# tracker.net
KiCad netlist of a schematic drawn in EAGLE
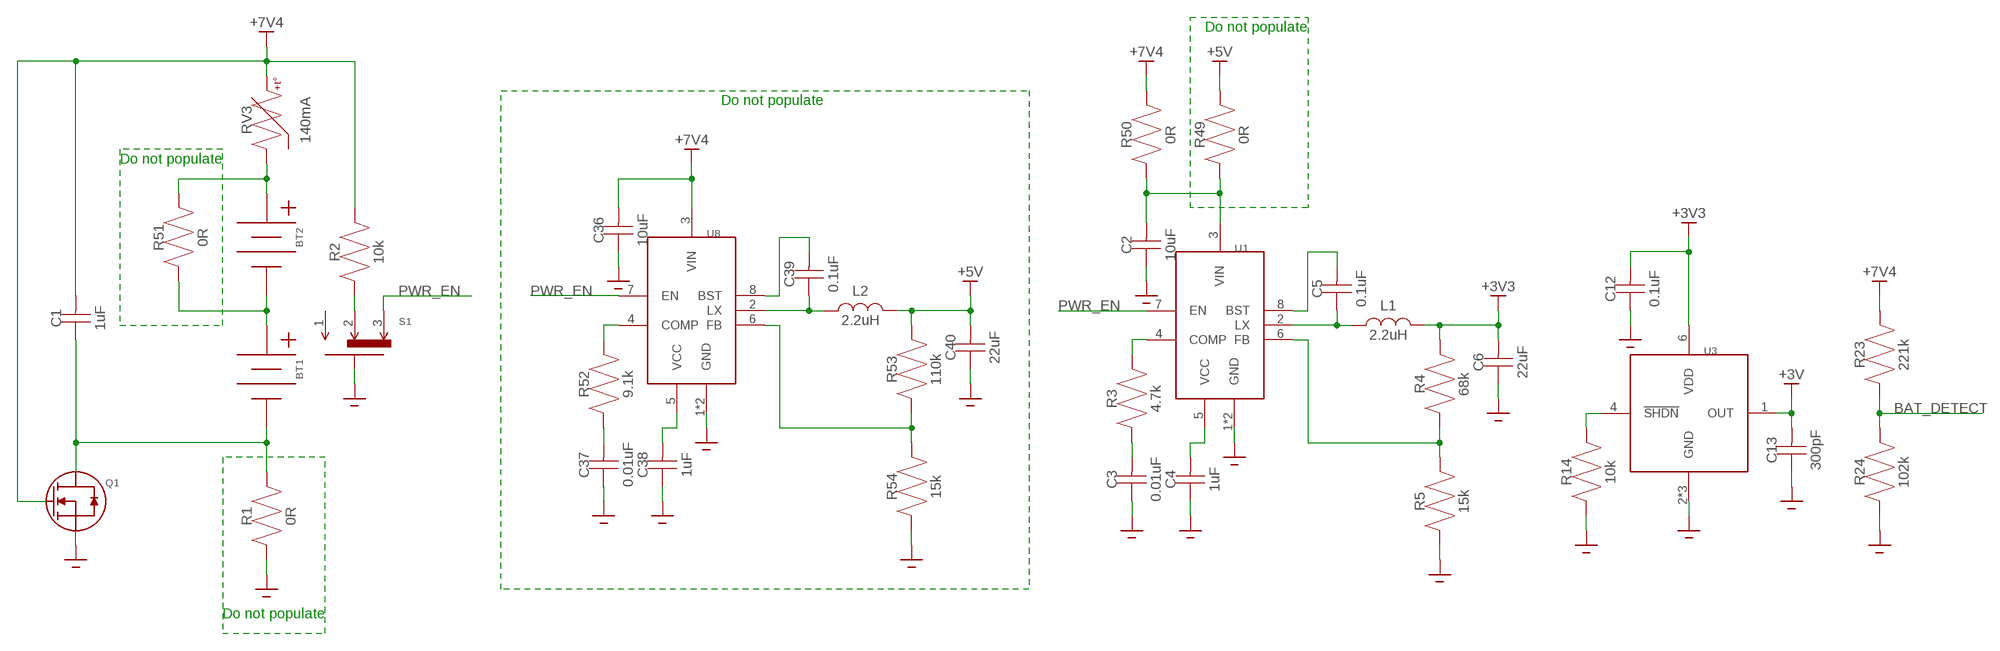
[diagram p0: schematic, sheet 1]
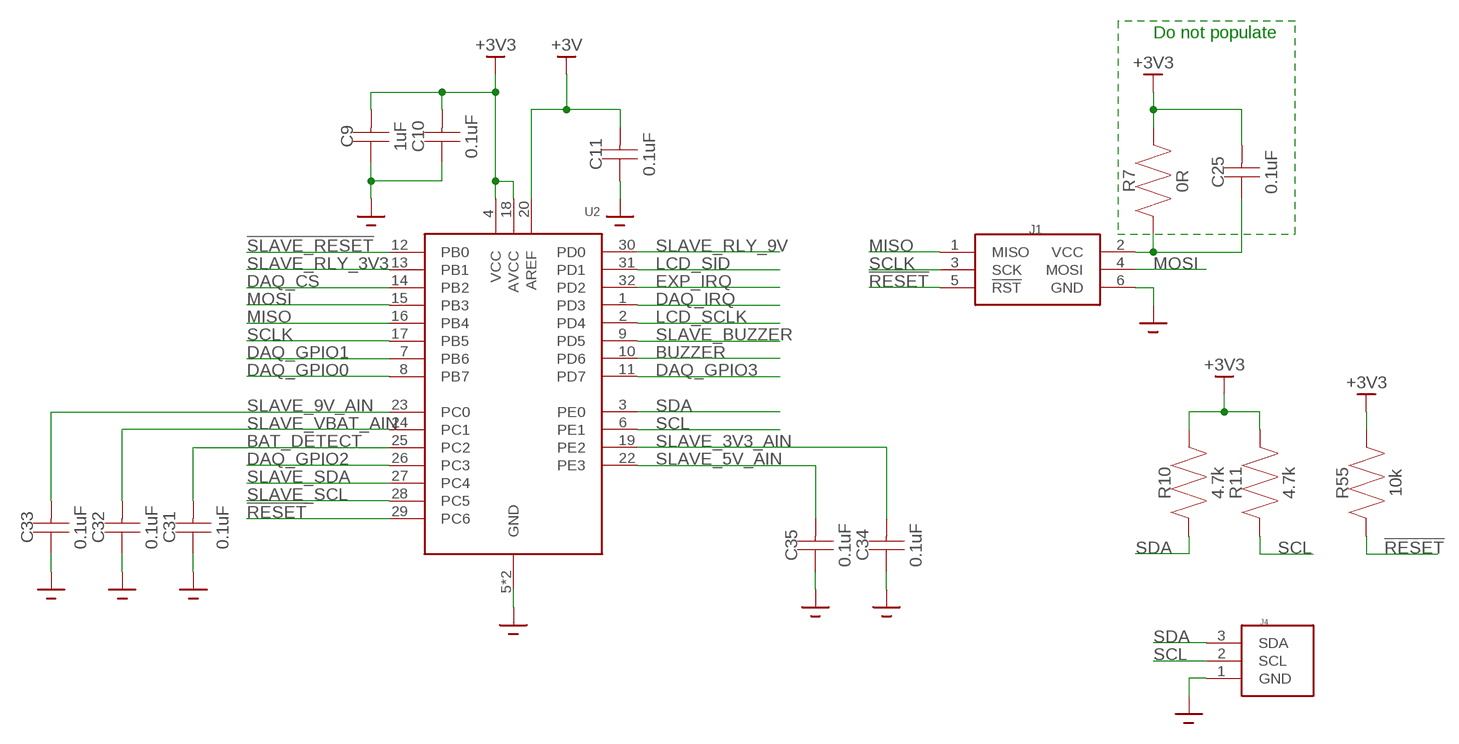
[diagram p1: schematic, sheet 2]
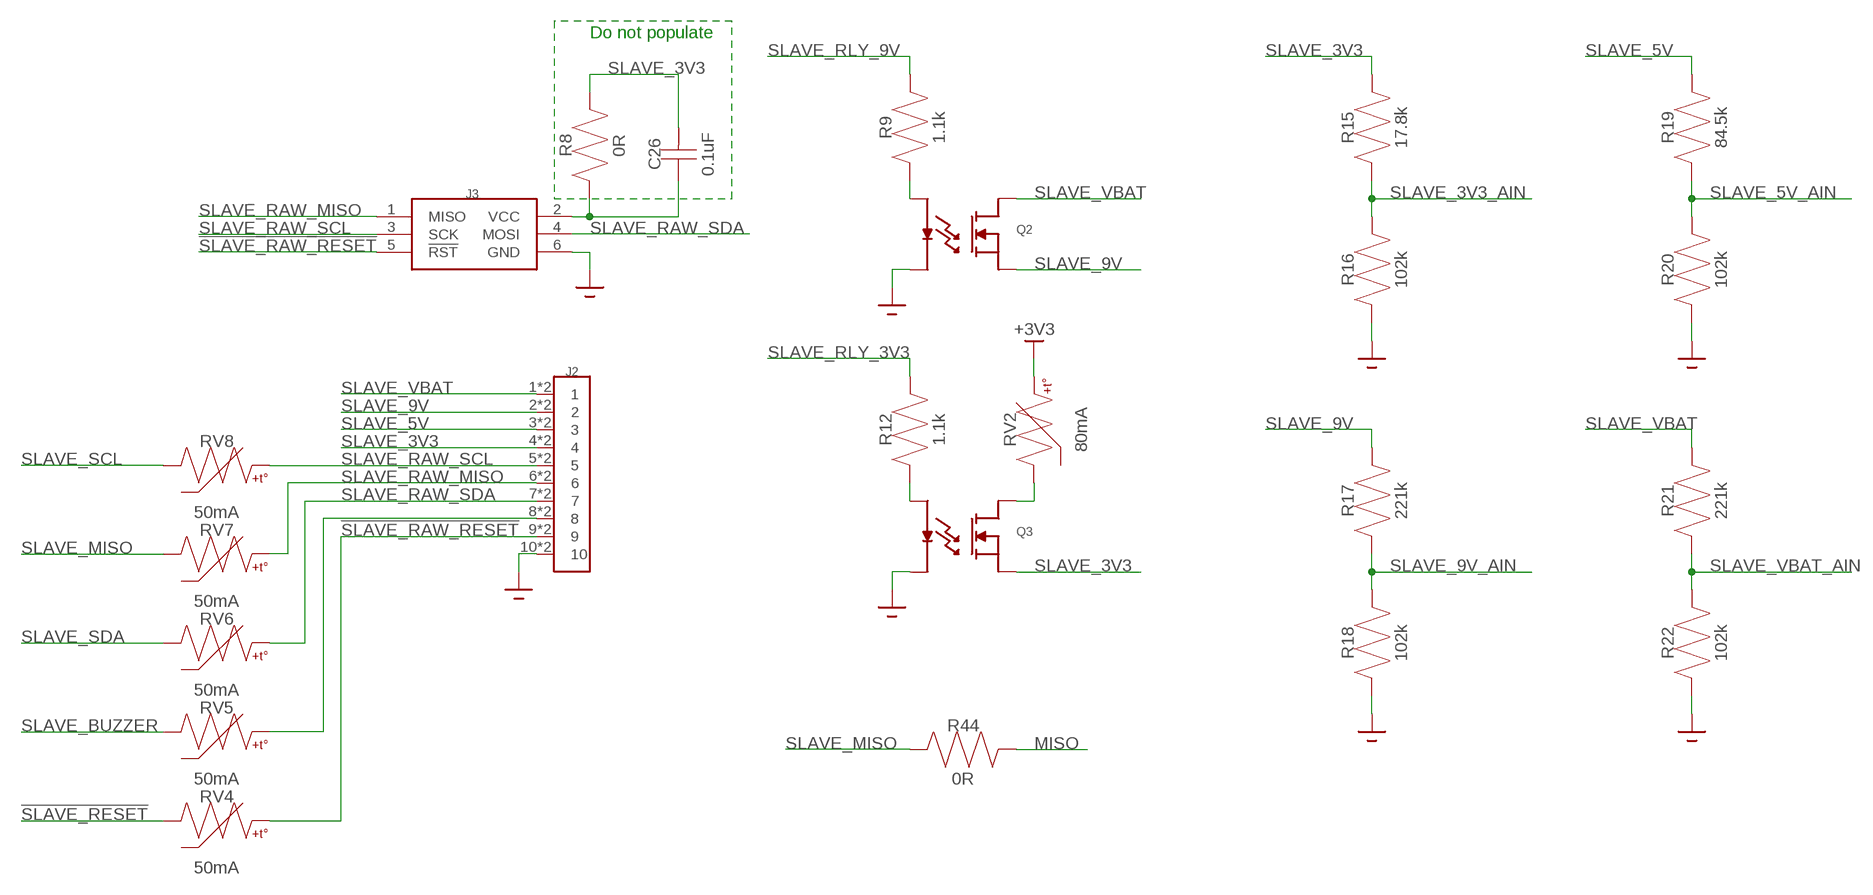
[diagram p2: schematic, sheet 3]
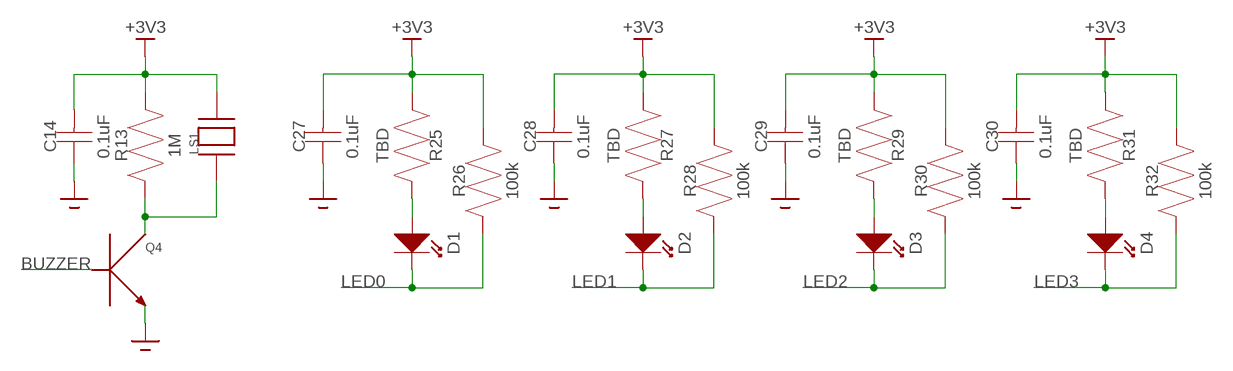
[diagram p3: schematic, sheet 4]
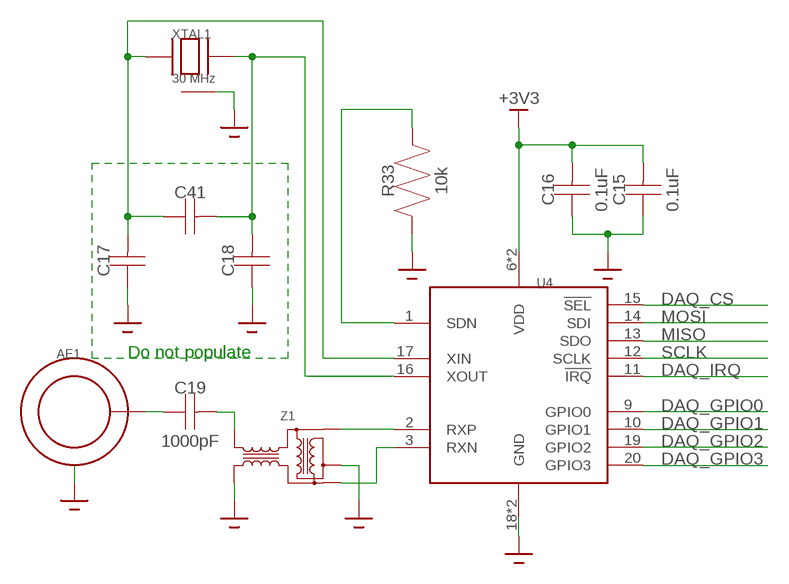
[diagram p4: schematic, sheet 5]
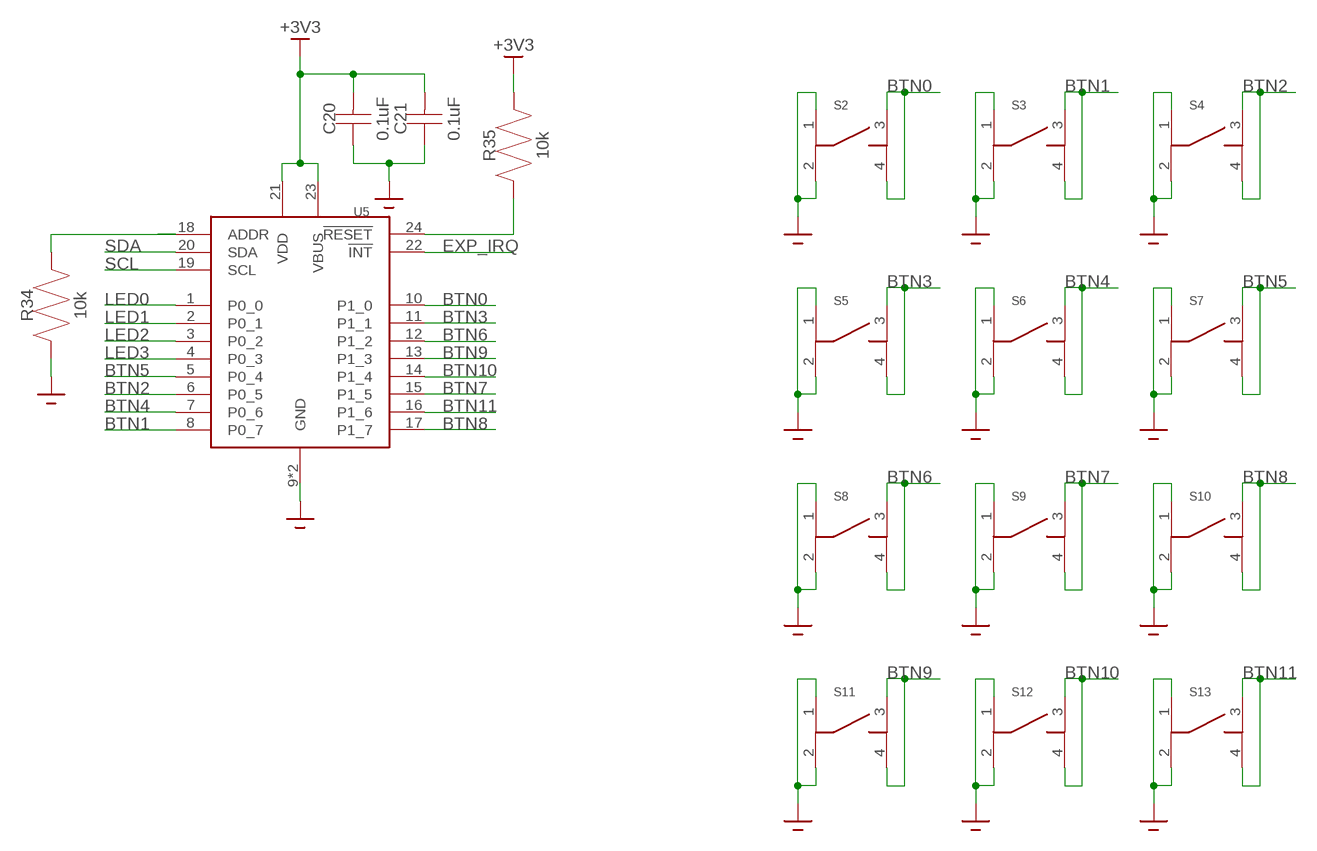
[diagram p5: schematic, sheet 6]
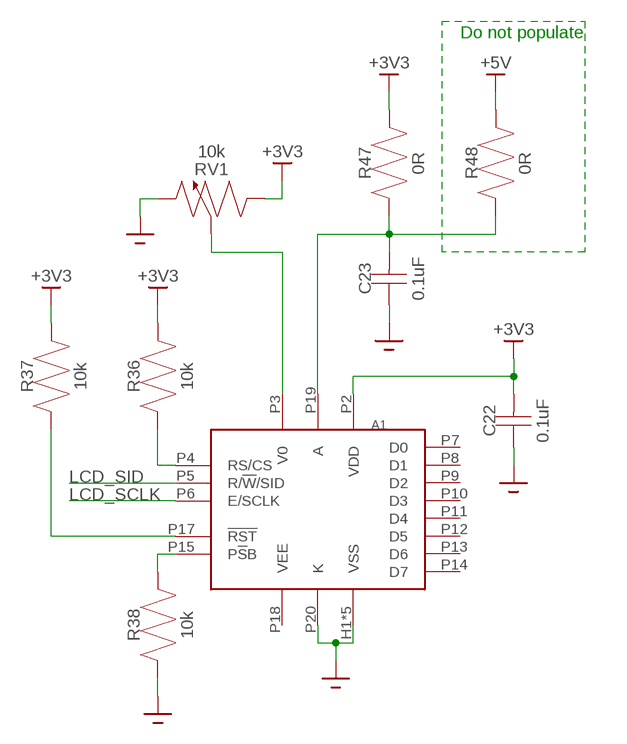
[diagram p6: schematic, sheet 7]
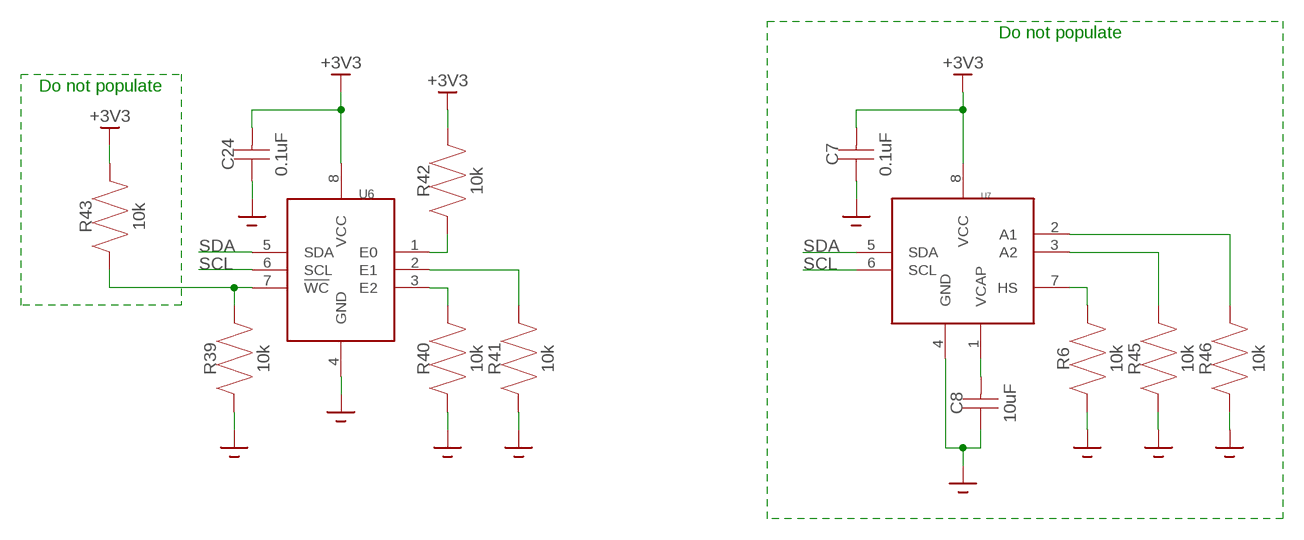
[diagram p7: schematic, sheet 8]

(export (version "E")
  (design (tool "Eeschema 10.0.6"))
  (components
    (comp (ref "A1")
      (value "LCD12864")
      (footprint "eagle-import:LCD12864")
      (libsource (lib "eagle-import") (part "LCD12864"))
    )
    (comp (ref "C22")
      (value "0.1uF")
      (footprint "eagle-import:0603")
      (libsource (lib "eagle-import") (part "CAPACITOR0603"))
    )
    (comp (ref "C23")
      (value "0.1uF")
      (footprint "eagle-import:0603")
      (libsource (lib "eagle-import") (part "CAPACITOR0603"))
    )
    (comp (ref "R36")
      (value "10k")
      (footprint "eagle-import:0603")
      (libsource (lib "eagle-import") (part "RESISTOR0603"))
    )
    (comp (ref "R37")
      (value "10k")
      (footprint "eagle-import:0603")
      (libsource (lib "eagle-import") (part "RESISTOR0603"))
    )
    (comp (ref "R38")
      (value "10k")
      (footprint "eagle-import:0603")
      (libsource (lib "eagle-import") (part "RESISTOR0603"))
    )
    (comp (ref "R47")
      (value "0R")
      (footprint "eagle-import:0603")
      (libsource (lib "eagle-import") (part "RESISTOR0603"))
    )
    (comp (ref "R48")
      (value "0R")
      (footprint "eagle-import:0603")
      (libsource (lib "eagle-import") (part "RESISTOR0603"))
    )
    (comp (ref "RV1")
      (value "10k")
      (footprint "eagle-import:TC33X-2")
      (libsource (lib "eagle-import") (part "TC33X-2"))
    )
    (comp (ref "C14")
      (value "0.1uF")
      (footprint "eagle-import:0603")
      (libsource (lib "eagle-import") (part "CAPACITOR0603"))
    )
    (comp (ref "C27")
      (value "0.1uF")
      (footprint "eagle-import:0603")
      (libsource (lib "eagle-import") (part "CAPACITOR0603"))
    )
    (comp (ref "C28")
      (value "0.1uF")
      (footprint "eagle-import:0603")
      (libsource (lib "eagle-import") (part "CAPACITOR0603"))
    )
    (comp (ref "C29")
      (value "0.1uF")
      (footprint "eagle-import:0603")
      (libsource (lib "eagle-import") (part "CAPACITOR0603"))
    )
    (comp (ref "C30")
      (value "0.1uF")
      (footprint "eagle-import:0603")
      (libsource (lib "eagle-import") (part "CAPACITOR0603"))
    )
    (comp (ref "D1")
      (value "LED")
      (footprint "eagle-import:0805")
      (libsource (lib "eagle-import") (part "LED"))
    )
    (comp (ref "D2")
      (value "LED")
      (footprint "eagle-import:0805")
      (libsource (lib "eagle-import") (part "LED"))
    )
    (comp (ref "D3")
      (value "LED")
      (footprint "eagle-import:0805")
      (libsource (lib "eagle-import") (part "LED"))
    )
    (comp (ref "D4")
      (value "LED")
      (footprint "eagle-import:0805")
      (libsource (lib "eagle-import") (part "LED"))
    )
    (comp (ref "LS1")
      (value "AT-1224-TWT-5V-2-R")
      (footprint "eagle-import:AT-1224-TWT-5V-2-R")
      (libsource (lib "eagle-import") (part "AT-1224-TWT-5V-2-R"))
    )
    (comp (ref "Q4")
      (value "MMBT3904")
      (footprint "eagle-import:MMBT3904")
      (libsource (lib "eagle-import") (part "MMBT3904"))
    )
    (comp (ref "R13")
      (value "1M")
      (footprint "eagle-import:0603")
      (libsource (lib "eagle-import") (part "RESISTOR0603"))
    )
    (comp (ref "R25")
      (value "TBD")
      (footprint "eagle-import:0603")
      (libsource (lib "eagle-import") (part "RESISTOR0603"))
    )
    (comp (ref "R26")
      (value "100k")
      (footprint "eagle-import:0603")
      (libsource (lib "eagle-import") (part "RESISTOR0603"))
    )
    (comp (ref "R27")
      (value "TBD")
      (footprint "eagle-import:0603")
      (libsource (lib "eagle-import") (part "RESISTOR0603"))
    )
    (comp (ref "R28")
      (value "100k")
      (footprint "eagle-import:0603")
      (libsource (lib "eagle-import") (part "RESISTOR0603"))
    )
    (comp (ref "R29")
      (value "TBD")
      (footprint "eagle-import:0603")
      (libsource (lib "eagle-import") (part "RESISTOR0603"))
    )
    (comp (ref "R30")
      (value "100k")
      (footprint "eagle-import:0603")
      (libsource (lib "eagle-import") (part "RESISTOR0603"))
    )
    (comp (ref "R31")
      (value "TBD")
      (footprint "eagle-import:0603")
      (libsource (lib "eagle-import") (part "RESISTOR0603"))
    )
    (comp (ref "R32")
      (value "100k")
      (footprint "eagle-import:0603")
      (libsource (lib "eagle-import") (part "RESISTOR0603"))
    )
    (comp (ref "AE1")
      (value "CON-SMA-EDGE-S")
      (footprint "eagle-import:CON-SMA-EDGE-S")
      (libsource (lib "eagle-import") (part "CON-SMA-EDGE-S"))
    )
    (comp (ref "C15")
      (value "0.1uF")
      (footprint "eagle-import:0603")
      (libsource (lib "eagle-import") (part "CAPACITOR0603"))
    )
    (comp (ref "C16")
      (value "0.1uF")
      (footprint "eagle-import:0603")
      (libsource (lib "eagle-import") (part "CAPACITOR0603"))
    )
    (comp (ref "C17")
      (value "CAPACITOR0603")
      (footprint "eagle-import:0603")
      (libsource (lib "eagle-import") (part "CAPACITOR0603"))
    )
    (comp (ref "C18")
      (value "CAPACITOR0603")
      (footprint "eagle-import:0603")
      (libsource (lib "eagle-import") (part "CAPACITOR0603"))
    )
    (comp (ref "C19")
      (value "1000pF")
      (footprint "eagle-import:0402")
      (libsource (lib "eagle-import") (part "CAPACITOR0402"))
    )
    (comp (ref "C41")
      (value "CAPACITOR0603")
      (footprint "eagle-import:0603")
      (libsource (lib "eagle-import") (part "CAPACITOR0603"))
    )
    (comp (ref "R33")
      (value "10k")
      (footprint "eagle-import:0603")
      (libsource (lib "eagle-import") (part "RESISTOR0603"))
    )
    (comp (ref "U4")
      (value "SI4362")
      (footprint "eagle-import:SI4362")
      (libsource (lib "eagle-import") (part "SI4362"))
    )
    (comp (ref "XTAL1")
      (value "30 MHz")
      (footprint "eagle-import:RH100")
      (libsource (lib "eagle-import") (part "RH100"))
    )
    (comp (ref "Z1")
      (value "TC1-1T-152X+")
      (footprint "eagle-import:TC1-1T-152X+")
      (libsource (lib "eagle-import") (part "TC1-1T-152X+"))
    )
    (comp (ref "C26")
      (value "0.1uF")
      (footprint "eagle-import:0603")
      (libsource (lib "eagle-import") (part "CAPACITOR0603"))
    )
    (comp (ref "J2")
      (value "5-5530843-0FEMALE")
      (footprint "eagle-import:5-5530843-0")
      (libsource (lib "eagle-import") (part "5-5530843-0FEMALE"))
    )
    (comp (ref "J3")
      (value "75869-131LF")
      (footprint "eagle-import:75869-131LF")
      (libsource (lib "eagle-import") (part "75869-131LF"))
    )
    (comp (ref "Q2")
      (value "CPC1002N")
      (footprint "eagle-import:CPC1002N")
      (libsource (lib "eagle-import") (part "CPC1002N"))
    )
    (comp (ref "Q3")
      (value "CPC1002N")
      (footprint "eagle-import:CPC1002N")
      (libsource (lib "eagle-import") (part "CPC1002N"))
    )
    (comp (ref "R8")
      (value "0R")
      (footprint "eagle-import:0603")
      (libsource (lib "eagle-import") (part "RESISTOR0603"))
    )
    (comp (ref "R9")
      (value "1.1k")
      (footprint "eagle-import:0603")
      (libsource (lib "eagle-import") (part "RESISTOR0603"))
    )
    (comp (ref "R12")
      (value "1.1k")
      (footprint "eagle-import:0603")
      (libsource (lib "eagle-import") (part "RESISTOR0603"))
    )
    (comp (ref "R15")
      (value "17.8k")
      (footprint "eagle-import:0603")
      (libsource (lib "eagle-import") (part "RESISTOR0603"))
    )
    (comp (ref "R16")
      (value "102k")
      (footprint "eagle-import:0603")
      (libsource (lib "eagle-import") (part "RESISTOR0603"))
    )
    (comp (ref "R17")
      (value "221k")
      (footprint "eagle-import:0603")
      (libsource (lib "eagle-import") (part "RESISTOR0603"))
    )
    (comp (ref "R18")
      (value "102k")
      (footprint "eagle-import:0603")
      (libsource (lib "eagle-import") (part "RESISTOR0603"))
    )
    (comp (ref "R19")
      (value "84.5k")
      (footprint "eagle-import:0603")
      (libsource (lib "eagle-import") (part "RESISTOR0603"))
    )
    (comp (ref "R20")
      (value "102k")
      (footprint "eagle-import:0603")
      (libsource (lib "eagle-import") (part "RESISTOR0603"))
    )
    (comp (ref "R21")
      (value "221k")
      (footprint "eagle-import:0603")
      (libsource (lib "eagle-import") (part "RESISTOR0603"))
    )
    (comp (ref "R22")
      (value "102k")
      (footprint "eagle-import:0603")
      (libsource (lib "eagle-import") (part "RESISTOR0603"))
    )
    (comp (ref "R44")
      (value "0R")
      (footprint "eagle-import:0603")
      (libsource (lib "eagle-import") (part "RESISTOR0603"))
    )
    (comp (ref "RV2")
      (value "80mA")
      (footprint "eagle-import:0603")
      (libsource (lib "eagle-import") (part "PTC0603"))
    )
    (comp (ref "RV4")
      (value "50mA")
      (footprint "eagle-import:0603")
      (libsource (lib "eagle-import") (part "PTC0603"))
    )
    (comp (ref "RV5")
      (value "50mA")
      (footprint "eagle-import:0603")
      (libsource (lib "eagle-import") (part "PTC0603"))
    )
    (comp (ref "RV6")
      (value "50mA")
      (footprint "eagle-import:0603")
      (libsource (lib "eagle-import") (part "PTC0603"))
    )
    (comp (ref "RV7")
      (value "50mA")
      (footprint "eagle-import:0603")
      (libsource (lib "eagle-import") (part "PTC0603"))
    )
    (comp (ref "RV8")
      (value "50mA")
      (footprint "eagle-import:0603")
      (libsource (lib "eagle-import") (part "PTC0603"))
    )
    (comp (ref "C20")
      (value "0.1uF")
      (footprint "eagle-import:0603")
      (libsource (lib "eagle-import") (part "CAPACITOR0603"))
    )
    (comp (ref "C21")
      (value "0.1uF")
      (footprint "eagle-import:0603")
      (libsource (lib "eagle-import") (part "CAPACITOR0603"))
    )
    (comp (ref "R34")
      (value "10k")
      (footprint "eagle-import:0603")
      (libsource (lib "eagle-import") (part "RESISTOR0603"))
    )
    (comp (ref "R35")
      (value "10k")
      (footprint "eagle-import:0603")
      (libsource (lib "eagle-import") (part "RESISTOR0603"))
    )
    (comp (ref "S2")
      (value "3-1825910")
      (footprint "eagle-import:3-1825910")
      (libsource (lib "eagle-import") (part "3-1825910"))
    )
    (comp (ref "S3")
      (value "3-1825910")
      (footprint "eagle-import:3-1825910")
      (libsource (lib "eagle-import") (part "3-1825910"))
    )
    (comp (ref "S4")
      (value "3-1825910")
      (footprint "eagle-import:3-1825910")
      (libsource (lib "eagle-import") (part "3-1825910"))
    )
    (comp (ref "S5")
      (value "3-1825910")
      (footprint "eagle-import:3-1825910")
      (libsource (lib "eagle-import") (part "3-1825910"))
    )
    (comp (ref "S6")
      (value "3-1825910")
      (footprint "eagle-import:3-1825910")
      (libsource (lib "eagle-import") (part "3-1825910"))
    )
    (comp (ref "S7")
      (value "3-1825910")
      (footprint "eagle-import:3-1825910")
      (libsource (lib "eagle-import") (part "3-1825910"))
    )
    (comp (ref "S8")
      (value "3-1825910")
      (footprint "eagle-import:3-1825910")
      (libsource (lib "eagle-import") (part "3-1825910"))
    )
    (comp (ref "S9")
      (value "3-1825910")
      (footprint "eagle-import:3-1825910")
      (libsource (lib "eagle-import") (part "3-1825910"))
    )
    (comp (ref "S10")
      (value "3-1825910")
      (footprint "eagle-import:3-1825910")
      (libsource (lib "eagle-import") (part "3-1825910"))
    )
    (comp (ref "S11")
      (value "3-1825910")
      (footprint "eagle-import:3-1825910")
      (libsource (lib "eagle-import") (part "3-1825910"))
    )
    (comp (ref "S12")
      (value "3-1825910")
      (footprint "eagle-import:3-1825910")
      (libsource (lib "eagle-import") (part "3-1825910"))
    )
    (comp (ref "S13")
      (value "3-1825910")
      (footprint "eagle-import:3-1825910")
      (libsource (lib "eagle-import") (part "3-1825910"))
    )
    (comp (ref "U5")
      (value "PCAL6416")
      (footprint "eagle-import:PCAL6416")
      (libsource (lib "eagle-import") (part "PCAL6416"))
    )
    (comp (ref "BT1")
      (value "18650")
      (footprint "eagle-import:18650")
      (libsource (lib "eagle-import") (part "18650"))
    )
    (comp (ref "BT2")
      (value "18650")
      (footprint "eagle-import:18650")
      (libsource (lib "eagle-import") (part "18650"))
    )
    (comp (ref "C1")
      (value "1uF")
      (footprint "eagle-import:0603")
      (libsource (lib "eagle-import") (part "CAPACITOR0603"))
    )
    (comp (ref "C2")
      (value "10uF")
      (footprint "eagle-import:0805")
      (libsource (lib "eagle-import") (part "CAPACITOR0805"))
    )
    (comp (ref "C3")
      (value "0.01uF")
      (footprint "eagle-import:0603")
      (libsource (lib "eagle-import") (part "CAPACITOR0603"))
    )
    (comp (ref "C4")
      (value "1uF")
      (footprint "eagle-import:0603")
      (libsource (lib "eagle-import") (part "CAPACITOR0603"))
    )
    (comp (ref "C5")
      (value "0.1uF")
      (footprint "eagle-import:0603")
      (libsource (lib "eagle-import") (part "CAPACITOR0603"))
    )
    (comp (ref "C6")
      (value "22uF")
      (footprint "eagle-import:0805")
      (libsource (lib "eagle-import") (part "CAPACITOR0805"))
    )
    (comp (ref "C12")
      (value "0.1uF")
      (footprint "eagle-import:0603")
      (libsource (lib "eagle-import") (part "CAPACITOR0603"))
    )
    (comp (ref "C13")
      (value "300pF")
      (footprint "eagle-import:0603")
      (libsource (lib "eagle-import") (part "CAPACITOR0603"))
    )
    (comp (ref "C36")
      (value "10uF")
      (footprint "eagle-import:0805")
      (libsource (lib "eagle-import") (part "CAPACITOR0805"))
    )
    (comp (ref "C37")
      (value "0.01uF")
      (footprint "eagle-import:0603")
      (libsource (lib "eagle-import") (part "CAPACITOR0603"))
    )
    (comp (ref "C38")
      (value "1uF")
      (footprint "eagle-import:0603")
      (libsource (lib "eagle-import") (part "CAPACITOR0603"))
    )
    (comp (ref "C39")
      (value "0.1uF")
      (footprint "eagle-import:0603")
      (libsource (lib "eagle-import") (part "CAPACITOR0603"))
    )
    (comp (ref "C40")
      (value "22uF")
      (footprint "eagle-import:0805")
      (libsource (lib "eagle-import") (part "CAPACITOR0805"))
    )
    (comp (ref "L1")
      (value "2.2uH")
      (footprint "eagle-import:0805")
      (libsource (lib "eagle-import") (part "INDUCTOR0805"))
    )
    (comp (ref "L2")
      (value "2.2uH")
      (footprint "eagle-import:0805")
      (libsource (lib "eagle-import") (part "INDUCTOR0805"))
    )
    (comp (ref "Q1")
      (value "DMG2302UK")
      (footprint "eagle-import:DMG2302UK")
      (libsource (lib "eagle-import") (part "DMG2302UK"))
    )
    (comp (ref "R1")
      (value "0R")
      (footprint "eagle-import:0603")
      (libsource (lib "eagle-import") (part "RESISTOR0603"))
    )
    (comp (ref "R2")
      (value "10k")
      (footprint "eagle-import:0603")
      (libsource (lib "eagle-import") (part "RESISTOR0603"))
    )
    (comp (ref "R3")
      (value "4.7k")
      (footprint "eagle-import:0603")
      (libsource (lib "eagle-import") (part "RESISTOR0603"))
    )
    (comp (ref "R4")
      (value "68k")
      (footprint "eagle-import:0603")
      (libsource (lib "eagle-import") (part "RESISTOR0603"))
    )
    (comp (ref "R5")
      (value "15k")
      (footprint "eagle-import:0603")
      (libsource (lib "eagle-import") (part "RESISTOR0603"))
    )
    (comp (ref "R14")
      (value "10k")
      (footprint "eagle-import:0603")
      (libsource (lib "eagle-import") (part "RESISTOR0603"))
    )
    (comp (ref "R23")
      (value "221k")
      (footprint "eagle-import:0603")
      (libsource (lib "eagle-import") (part "RESISTOR0603"))
    )
    (comp (ref "R24")
      (value "102k")
      (footprint "eagle-import:0603")
      (libsource (lib "eagle-import") (part "RESISTOR0603"))
    )
    (comp (ref "R49")
      (value "0R")
      (footprint "eagle-import:0603")
      (libsource (lib "eagle-import") (part "RESISTOR0603"))
    )
    (comp (ref "R50")
      (value "0R")
      (footprint "eagle-import:0603")
      (libsource (lib "eagle-import") (part "RESISTOR0603"))
    )
    (comp (ref "R51")
      (value "0R")
      (footprint "eagle-import:0603")
      (libsource (lib "eagle-import") (part "RESISTOR0603"))
    )
    (comp (ref "R52")
      (value "9.1k")
      (footprint "eagle-import:0603")
      (libsource (lib "eagle-import") (part "RESISTOR0603"))
    )
    (comp (ref "R53")
      (value "110k")
      (footprint "eagle-import:0603")
      (libsource (lib "eagle-import") (part "RESISTOR0603"))
    )
    (comp (ref "R54")
      (value "15k")
      (footprint "eagle-import:0603")
      (libsource (lib "eagle-import") (part "RESISTOR0603"))
    )
    (comp (ref "RV3")
      (value "140mA")
      (footprint "eagle-import:1812")
      (libsource (lib "eagle-import") (part "PTC1812"))
    )
    (comp (ref "S1")
      (value "OS102011MA1QN1")
      (footprint "eagle-import:OS102011MA1QN1")
      (libsource (lib "eagle-import") (part "OS102011MA1QN1"))
    )
    (comp (ref "U1")
      (value "AOZ6662DI")
      (footprint "eagle-import:AOZ6662DI")
      (libsource (lib "eagle-import") (part "AOZ6662DI"))
    )
    (comp (ref "U3")
      (value "MCP1501")
      (footprint "eagle-import:SOT95P280X145-6N")
      (libsource (lib "eagle-import") (part "MCP1501"))
    )
    (comp (ref "U8")
      (value "AOZ6662DI")
      (footprint "eagle-import:AOZ6662DI")
      (libsource (lib "eagle-import") (part "AOZ6662DI"))
    )
    (comp (ref "C9")
      (value "1uF")
      (footprint "eagle-import:0603")
      (libsource (lib "eagle-import") (part "CAPACITOR0603"))
    )
    (comp (ref "C10")
      (value "0.1uF")
      (footprint "eagle-import:0603")
      (libsource (lib "eagle-import") (part "CAPACITOR0603"))
    )
    (comp (ref "C11")
      (value "0.1uF")
      (footprint "eagle-import:0603")
      (libsource (lib "eagle-import") (part "CAPACITOR0603"))
    )
    (comp (ref "C25")
      (value "0.1uF")
      (footprint "eagle-import:0603")
      (libsource (lib "eagle-import") (part "CAPACITOR0603"))
    )
    (comp (ref "C31")
      (value "0.1uF")
      (footprint "eagle-import:0603")
      (libsource (lib "eagle-import") (part "CAPACITOR0603"))
    )
    (comp (ref "C32")
      (value "0.1uF")
      (footprint "eagle-import:0603")
      (libsource (lib "eagle-import") (part "CAPACITOR0603"))
    )
    (comp (ref "C33")
      (value "0.1uF")
      (footprint "eagle-import:0603")
      (libsource (lib "eagle-import") (part "CAPACITOR0603"))
    )
    (comp (ref "C34")
      (value "0.1uF")
      (footprint "eagle-import:0603")
      (libsource (lib "eagle-import") (part "CAPACITOR0603"))
    )
    (comp (ref "C35")
      (value "0.1uF")
      (footprint "eagle-import:0603")
      (libsource (lib "eagle-import") (part "CAPACITOR0603"))
    )
    (comp (ref "J1")
      (value "75869-131LF")
      (footprint "eagle-import:75869-131LF")
      (libsource (lib "eagle-import") (part "75869-131LF"))
    )
    (comp (ref "J4")
      (value "640456-3")
      (footprint "eagle-import:640456-3")
      (libsource (lib "eagle-import") (part "640456-3"))
    )
    (comp (ref "R7")
      (value "0R")
      (footprint "eagle-import:0603")
      (libsource (lib "eagle-import") (part "RESISTOR0603"))
    )
    (comp (ref "R10")
      (value "4.7k")
      (footprint "eagle-import:0603")
      (libsource (lib "eagle-import") (part "RESISTOR0603"))
    )
    (comp (ref "R11")
      (value "4.7k")
      (footprint "eagle-import:0603")
      (libsource (lib "eagle-import") (part "RESISTOR0603"))
    )
    (comp (ref "R55")
      (value "10k")
      (footprint "eagle-import:0603")
      (libsource (lib "eagle-import") (part "RESISTOR0603"))
    )
    (comp (ref "U2")
      (value "ATMEGA328PB32-TQFP")
      (footprint "eagle-import:ATMEGA328PB")
      (libsource (lib "eagle-import") (part "ATMEGA328PB32-TQFP"))
    )
    (comp (ref "C7")
      (value "0.1uF")
      (footprint "eagle-import:0603")
      (libsource (lib "eagle-import") (part "CAPACITOR0603"))
    )
    (comp (ref "C8")
      (value "10uF")
      (footprint "eagle-import:0805")
      (libsource (lib "eagle-import") (part "CAPACITOR0805"))
    )
    (comp (ref "C24")
      (value "0.1uF")
      (footprint "eagle-import:0603")
      (libsource (lib "eagle-import") (part "CAPACITOR0603"))
    )
    (comp (ref "R6")
      (value "10k")
      (footprint "eagle-import:0603")
      (libsource (lib "eagle-import") (part "RESISTOR0603"))
    )
    (comp (ref "R39")
      (value "10k")
      (footprint "eagle-import:0603")
      (libsource (lib "eagle-import") (part "RESISTOR0603"))
    )
    (comp (ref "R40")
      (value "10k")
      (footprint "eagle-import:0603")
      (libsource (lib "eagle-import") (part "RESISTOR0603"))
    )
    (comp (ref "R41")
      (value "10k")
      (footprint "eagle-import:0603")
      (libsource (lib "eagle-import") (part "RESISTOR0603"))
    )
    (comp (ref "R42")
      (value "10k")
      (footprint "eagle-import:0603")
      (libsource (lib "eagle-import") (part "RESISTOR0603"))
    )
    (comp (ref "R43")
      (value "10k")
      (footprint "eagle-import:0603")
      (libsource (lib "eagle-import") (part "RESISTOR0603"))
    )
    (comp (ref "R45")
      (value "10k")
      (footprint "eagle-import:0603")
      (libsource (lib "eagle-import") (part "RESISTOR0603"))
    )
    (comp (ref "R46")
      (value "10k")
      (footprint "eagle-import:0603")
      (libsource (lib "eagle-import") (part "RESISTOR0603"))
    )
    (comp (ref "U6")
      (value "M24")
      (footprint "eagle-import:M24")
      (libsource (lib "eagle-import") (part "M24"))
    )
    (comp (ref "U7")
      (value "47L16")
      (footprint "eagle-import:47L16")
      (libsource (lib "eagle-import") (part "47L16"))
    )
  )
  (nets
    (net (code "1") (name "+3V") (class "Default")
      (node (ref "C11") (pin "P$2") (pinfunction "P$2_P$2") (pintype "passive"))
      (node (ref "C13") (pin "P$2") (pinfunction "P$2_P$2") (pintype "passive"))
      (node (ref "U2") (pin "20") (pinfunction "AREF_20") (pintype "power_in"))
      (node (ref "U3") (pin "1") (pinfunction "OUT_1") (pintype "power_in"))
    )
    (net (code "2") (name "+3V3") (class "Default")
      (node (ref "A1") (pin "P2") (pinfunction "VDD_P2") (pintype "power_in"))
      (node (ref "C10") (pin "P$2") (pinfunction "P$2_P$2") (pintype "passive"))
      (node (ref "C12") (pin "P$2") (pinfunction "P$2_P$2") (pintype "passive"))
      (node (ref "C14") (pin "P$2") (pinfunction "P$2_P$2") (pintype "passive"))
      (node (ref "C15") (pin "P$2") (pinfunction "P$2_P$2") (pintype "passive"))
      (node (ref "C16") (pin "P$2") (pinfunction "P$2_P$2") (pintype "passive"))
      (node (ref "C20") (pin "P$2") (pinfunction "P$2_P$2") (pintype "passive"))
      (node (ref "C21") (pin "P$2") (pinfunction "P$2_P$2") (pintype "passive"))
      (node (ref "C22") (pin "P$2") (pinfunction "P$2_P$2") (pintype "passive"))
      (node (ref "C24") (pin "P$2") (pinfunction "P$2_P$2") (pintype "passive"))
      (node (ref "C25") (pin "P$2") (pinfunction "P$2_P$2") (pintype "passive"))
      (node (ref "C27") (pin "P$2") (pinfunction "P$2_P$2") (pintype "passive"))
      (node (ref "C28") (pin "P$2") (pinfunction "P$2_P$2") (pintype "passive"))
      (node (ref "C29") (pin "P$2") (pinfunction "P$2_P$2") (pintype "passive"))
      (node (ref "C30") (pin "P$2") (pinfunction "P$2_P$2") (pintype "passive"))
      (node (ref "C6") (pin "P$2") (pinfunction "P$2_P$2") (pintype "passive"))
      (node (ref "C7") (pin "P$2") (pinfunction "P$2_P$2") (pintype "passive"))
      (node (ref "C9") (pin "P$2") (pinfunction "P$2_P$2") (pintype "passive"))
      (node (ref "L1") (pin "P$2") (pinfunction "P$2_P$2") (pintype "passive"))
      (node (ref "LS1") (pin "2") (pinfunction "P$2_2") (pintype "passive"))
      (node (ref "R10") (pin "P$2") (pinfunction "P$2_P$2") (pintype "passive"))
      (node (ref "R11") (pin "P$2") (pinfunction "P$2_P$2") (pintype "passive"))
      (node (ref "R13") (pin "P$2") (pinfunction "P$2_P$2") (pintype "passive"))
      (node (ref "R25") (pin "P$1") (pinfunction "P$1_P$1") (pintype "passive"))
      (node (ref "R26") (pin "P$2") (pinfunction "P$2_P$2") (pintype "passive"))
      (node (ref "R27") (pin "P$1") (pinfunction "P$1_P$1") (pintype "passive"))
      (node (ref "R28") (pin "P$2") (pinfunction "P$2_P$2") (pintype "passive"))
      (node (ref "R29") (pin "P$1") (pinfunction "P$1_P$1") (pintype "passive"))
      (node (ref "R30") (pin "P$2") (pinfunction "P$2_P$2") (pintype "passive"))
      (node (ref "R31") (pin "P$1") (pinfunction "P$1_P$1") (pintype "passive"))
      (node (ref "R32") (pin "P$2") (pinfunction "P$2_P$2") (pintype "passive"))
      (node (ref "R35") (pin "P$2") (pinfunction "P$2_P$2") (pintype "passive"))
      (node (ref "R36") (pin "P$2") (pinfunction "P$2_P$2") (pintype "passive"))
      (node (ref "R37") (pin "P$2") (pinfunction "P$2_P$2") (pintype "passive"))
      (node (ref "R4") (pin "P$2") (pinfunction "P$2_P$2") (pintype "passive"))
      (node (ref "R42") (pin "P$2") (pinfunction "P$2_P$2") (pintype "passive"))
      (node (ref "R43") (pin "P$2") (pinfunction "P$2_P$2") (pintype "passive"))
      (node (ref "R47") (pin "P$2") (pinfunction "P$2_P$2") (pintype "passive"))
      (node (ref "R55") (pin "P$2") (pinfunction "P$2_P$2") (pintype "passive"))
      (node (ref "R7") (pin "P$2") (pinfunction "P$2_P$2") (pintype "passive"))
      (node (ref "RV1") (pin "1") (pinfunction "CCW_1") (pintype "passive"))
      (node (ref "RV2") (pin "P$2") (pinfunction "P$2_P$2") (pintype "passive"))
      (node (ref "U2") (pin "18") (pinfunction "AVCC_18") (pintype "power_in"))
      (node (ref "U2") (pin "4") (pinfunction "VCC_4") (pintype "power_in"))
      (node (ref "U3") (pin "6") (pinfunction "VDD_6") (pintype "power_in"))
      (node (ref "U4") (pin "6") (pinfunction "VDD_6") (pintype "power_in"))
      (node (ref "U4") (pin "8") (pinfunction "VDD_8") (pintype "power_in"))
      (node (ref "U5") (pin "21") (pinfunction "VDD_21") (pintype "power_in"))
      (node (ref "U5") (pin "23") (pinfunction "VBUS_23") (pintype "power_in"))
      (node (ref "U6") (pin "8") (pinfunction "VCC_8") (pintype "power_in"))
      (node (ref "U7") (pin "8") (pinfunction "VCC_8") (pintype "power_in"))
    )
    (net (code "3") (name "+5V") (class "Default")
      (node (ref "C40") (pin "P$2") (pinfunction "P$2_P$2") (pintype "passive"))
      (node (ref "L2") (pin "P$2") (pinfunction "P$2_P$2") (pintype "passive"))
      (node (ref "R48") (pin "P$2") (pinfunction "P$2_P$2") (pintype "passive"))
      (node (ref "R49") (pin "P$2") (pinfunction "P$2_P$2") (pintype "passive"))
      (node (ref "R53") (pin "P$2") (pinfunction "P$2_P$2") (pintype "passive"))
    )
    (net (code "4") (name "+7V4V") (class "Default")
      (node (ref "C1") (pin "P$2") (pinfunction "P$2_P$2") (pintype "passive"))
      (node (ref "C36") (pin "P$2") (pinfunction "P$2_P$2") (pintype "passive"))
      (node (ref "Q1") (pin "1") (pinfunction "G_1") (pintype "bidirectional"))
      (node (ref "R2") (pin "P$2") (pinfunction "P$2_P$2") (pintype "passive"))
      (node (ref "R23") (pin "P$2") (pinfunction "P$2_P$2") (pintype "passive"))
      (node (ref "R50") (pin "P$2") (pinfunction "P$2_P$2") (pintype "passive"))
      (node (ref "RV3") (pin "P$2") (pinfunction "P$2_P$2") (pintype "passive"))
      (node (ref "U8") (pin "3") (pinfunction "VIN_3") (pintype "power_in"))
    )
    (net (code "5") (name "BAT_DETECT") (class "Default")
      (node (ref "C31") (pin "P$2") (pinfunction "P$2_P$2") (pintype "passive"))
      (node (ref "R23") (pin "P$1") (pinfunction "P$1_P$1") (pintype "passive"))
      (node (ref "R24") (pin "P$2") (pinfunction "P$2_P$2") (pintype "passive"))
      (node (ref "U2") (pin "25") (pinfunction "PC2_25") (pintype "bidirectional"))
    )
    (net (code "6") (name "BTN0") (class "Default")
      (node (ref "S2") (pin "3") (pinfunction "4_3") (pintype "passive"))
      (node (ref "S2") (pin "4") (pinfunction "3_4") (pintype "passive"))
      (node (ref "U5") (pin "10") (pinfunction "P1_0_10") (pintype "bidirectional"))
    )
    (net (code "7") (name "BTN1") (class "Default")
      (node (ref "S3") (pin "3") (pinfunction "4_3") (pintype "passive"))
      (node (ref "S3") (pin "4") (pinfunction "3_4") (pintype "passive"))
      (node (ref "U5") (pin "8") (pinfunction "P0_7_8") (pintype "bidirectional"))
    )
    (net (code "8") (name "BTN2") (class "Default")
      (node (ref "S4") (pin "3") (pinfunction "4_3") (pintype "passive"))
      (node (ref "S4") (pin "4") (pinfunction "3_4") (pintype "passive"))
      (node (ref "U5") (pin "6") (pinfunction "P0_5_6") (pintype "bidirectional"))
    )
    (net (code "9") (name "BTN3") (class "Default")
      (node (ref "S5") (pin "3") (pinfunction "4_3") (pintype "passive"))
      (node (ref "S5") (pin "4") (pinfunction "3_4") (pintype "passive"))
      (node (ref "U5") (pin "11") (pinfunction "P1_1_11") (pintype "bidirectional"))
    )
    (net (code "10") (name "BTN4") (class "Default")
      (node (ref "S6") (pin "3") (pinfunction "4_3") (pintype "passive"))
      (node (ref "S6") (pin "4") (pinfunction "3_4") (pintype "passive"))
      (node (ref "U5") (pin "7") (pinfunction "P0_6_7") (pintype "bidirectional"))
    )
    (net (code "11") (name "BTN5") (class "Default")
      (node (ref "S7") (pin "3") (pinfunction "4_3") (pintype "passive"))
      (node (ref "S7") (pin "4") (pinfunction "3_4") (pintype "passive"))
      (node (ref "U5") (pin "5") (pinfunction "P0_4_5") (pintype "bidirectional"))
    )
    (net (code "12") (name "BTN6") (class "Default")
      (node (ref "S8") (pin "3") (pinfunction "4_3") (pintype "passive"))
      (node (ref "S8") (pin "4") (pinfunction "3_4") (pintype "passive"))
      (node (ref "U5") (pin "12") (pinfunction "P1_2_12") (pintype "bidirectional"))
    )
    (net (code "13") (name "BTN7") (class "Default")
      (node (ref "S9") (pin "3") (pinfunction "4_3") (pintype "passive"))
      (node (ref "S9") (pin "4") (pinfunction "3_4") (pintype "passive"))
      (node (ref "U5") (pin "15") (pinfunction "P1_5_15") (pintype "bidirectional"))
    )
    (net (code "14") (name "BTN8") (class "Default")
      (node (ref "S10") (pin "3") (pinfunction "4_3") (pintype "passive"))
      (node (ref "S10") (pin "4") (pinfunction "3_4") (pintype "passive"))
      (node (ref "U5") (pin "17") (pinfunction "P1_7_17") (pintype "bidirectional"))
    )
    (net (code "15") (name "BTN9") (class "Default")
      (node (ref "S11") (pin "3") (pinfunction "4_3") (pintype "passive"))
      (node (ref "S11") (pin "4") (pinfunction "3_4") (pintype "passive"))
      (node (ref "U5") (pin "13") (pinfunction "P1_3_13") (pintype "bidirectional"))
    )
    (net (code "16") (name "BTN10") (class "Default")
      (node (ref "S12") (pin "3") (pinfunction "4_3") (pintype "passive"))
      (node (ref "S12") (pin "4") (pinfunction "3_4") (pintype "passive"))
      (node (ref "U5") (pin "14") (pinfunction "P1_4_14") (pintype "bidirectional"))
    )
    (net (code "17") (name "BTN11") (class "Default")
      (node (ref "S13") (pin "3") (pinfunction "4_3") (pintype "passive"))
      (node (ref "S13") (pin "4") (pinfunction "3_4") (pintype "passive"))
      (node (ref "U5") (pin "16") (pinfunction "P1_6_16") (pintype "bidirectional"))
    )
    (net (code "18") (name "BUZZER") (class "Default")
      (node (ref "Q4") (pin "1") (pinfunction "B_1") (pintype "bidirectional"))
      (node (ref "U2") (pin "10") (pinfunction "PD6_10") (pintype "bidirectional"))
    )
    (net (code "19") (name "DAQ_CS") (class "Default")
      (node (ref "U2") (pin "14") (pinfunction "PB2_14") (pintype "bidirectional"))
      (node (ref "U4") (pin "15") (pinfunction "~{SEL}_15") (pintype "input"))
    )
    (net (code "20") (name "DAQ_GPIO0") (class "Default")
      (node (ref "U2") (pin "8") (pinfunction "PB7_8") (pintype "bidirectional"))
      (node (ref "U4") (pin "9") (pinfunction "GPIO0_9") (pintype "bidirectional"))
    )
    (net (code "21") (name "DAQ_GPIO1") (class "Default")
      (node (ref "U2") (pin "7") (pinfunction "PB6_7") (pintype "bidirectional"))
      (node (ref "U4") (pin "10") (pinfunction "GPIO1_10") (pintype "bidirectional"))
    )
    (net (code "22") (name "DAQ_GPIO2") (class "Default")
      (node (ref "U2") (pin "26") (pinfunction "PC3_26") (pintype "bidirectional"))
      (node (ref "U4") (pin "19") (pinfunction "GPIO2_19") (pintype "bidirectional"))
    )
    (net (code "23") (name "DAQ_GPIO3") (class "Default")
      (node (ref "U2") (pin "11") (pinfunction "PD7_11") (pintype "bidirectional"))
      (node (ref "U4") (pin "20") (pinfunction "GPIO3_20") (pintype "bidirectional"))
    )
    (net (code "24") (name "DAQ_IRQ") (class "Default")
      (node (ref "U2") (pin "1") (pinfunction "PD3_1") (pintype "bidirectional"))
      (node (ref "U4") (pin "11") (pinfunction "~{IRQ}_11") (pintype "output"))
    )
    (net (code "25") (name "EXP_IRQ") (class "Default")
      (node (ref "U2") (pin "32") (pinfunction "PD2_32") (pintype "bidirectional"))
      (node (ref "U5") (pin "22") (pinfunction "~{INT}_22") (pintype "output"))
    )
    (net (code "26") (name "GND") (class "Default")
      (node (ref "A1") (pin "H1") (pinfunction "VSS_H1") (pintype "passive"))
      (node (ref "A1") (pin "H2") (pinfunction "VSS_H2") (pintype "passive"))
      (node (ref "A1") (pin "H3") (pinfunction "VSS_H3") (pintype "passive"))
      (node (ref "A1") (pin "H4") (pinfunction "VSS_H4") (pintype "passive"))
      (node (ref "A1") (pin "P1") (pinfunction "VSS_P1") (pintype "passive"))
      (node (ref "A1") (pin "P20") (pinfunction "K_P20") (pintype "passive"))
      (node (ref "AE1") (pin "GND1") (pinfunction "GND_GND1") (pintype "passive"))
      (node (ref "AE1") (pin "GND2") (pinfunction "GND_GND2") (pintype "passive"))
      (node (ref "AE1") (pin "GND3") (pinfunction "GND_GND3") (pintype "passive"))
      (node (ref "AE1") (pin "GND4") (pinfunction "GND_GND4") (pintype "passive"))
      (node (ref "C10") (pin "P$1") (pinfunction "P$1_P$1") (pintype "passive"))
      (node (ref "C11") (pin "P$1") (pinfunction "P$1_P$1") (pintype "passive"))
      (node (ref "C12") (pin "P$1") (pinfunction "P$1_P$1") (pintype "passive"))
      (node (ref "C13") (pin "P$1") (pinfunction "P$1_P$1") (pintype "passive"))
      (node (ref "C14") (pin "P$1") (pinfunction "P$1_P$1") (pintype "passive"))
      (node (ref "C15") (pin "P$1") (pinfunction "P$1_P$1") (pintype "passive"))
      (node (ref "C16") (pin "P$1") (pinfunction "P$1_P$1") (pintype "passive"))
      (node (ref "C17") (pin "P$1") (pinfunction "P$1_P$1") (pintype "passive"))
      (node (ref "C18") (pin "P$1") (pinfunction "P$1_P$1") (pintype "passive"))
      (node (ref "C2") (pin "P$1") (pinfunction "P$1_P$1") (pintype "passive"))
      (node (ref "C20") (pin "P$1") (pinfunction "P$1_P$1") (pintype "passive"))
      (node (ref "C21") (pin "P$1") (pinfunction "P$1_P$1") (pintype "passive"))
      (node (ref "C22") (pin "P$1") (pinfunction "P$1_P$1") (pintype "passive"))
      (node (ref "C23") (pin "P$1") (pinfunction "P$1_P$1") (pintype "passive"))
      (node (ref "C24") (pin "P$1") (pinfunction "P$1_P$1") (pintype "passive"))
      (node (ref "C27") (pin "P$1") (pinfunction "P$1_P$1") (pintype "passive"))
      (node (ref "C28") (pin "P$1") (pinfunction "P$1_P$1") (pintype "passive"))
      (node (ref "C29") (pin "P$1") (pinfunction "P$1_P$1") (pintype "passive"))
      (node (ref "C3") (pin "P$1") (pinfunction "P$1_P$1") (pintype "passive"))
      (node (ref "C30") (pin "P$1") (pinfunction "P$1_P$1") (pintype "passive"))
      (node (ref "C31") (pin "P$1") (pinfunction "P$1_P$1") (pintype "passive"))
      (node (ref "C32") (pin "P$1") (pinfunction "P$1_P$1") (pintype "passive"))
      (node (ref "C33") (pin "P$1") (pinfunction "P$1_P$1") (pintype "passive"))
      (node (ref "C34") (pin "P$1") (pinfunction "P$1_P$1") (pintype "passive"))
      (node (ref "C35") (pin "P$1") (pinfunction "P$1_P$1") (pintype "passive"))
      (node (ref "C36") (pin "P$1") (pinfunction "P$1_P$1") (pintype "passive"))
      (node (ref "C37") (pin "P$1") (pinfunction "P$1_P$1") (pintype "passive"))
      (node (ref "C38") (pin "P$1") (pinfunction "P$1_P$1") (pintype "passive"))
      (node (ref "C4") (pin "P$1") (pinfunction "P$1_P$1") (pintype "passive"))
      (node (ref "C40") (pin "P$1") (pinfunction "P$1_P$1") (pintype "passive"))
      (node (ref "C6") (pin "P$1") (pinfunction "P$1_P$1") (pintype "passive"))
      (node (ref "C7") (pin "P$1") (pinfunction "P$1_P$1") (pintype "passive"))
      (node (ref "C8") (pin "P$1") (pinfunction "P$1_P$1") (pintype "passive"))
      (node (ref "C9") (pin "P$1") (pinfunction "P$1_P$1") (pintype "passive"))
      (node (ref "J1") (pin "6") (pinfunction "GND_6") (pintype "passive"))
      (node (ref "J2") (pin "10") (pinfunction "10_10") (pintype "power_in"))
      (node (ref "J2") (pin "20") (pinfunction "10_20") (pintype "power_in"))
      (node (ref "J3") (pin "6") (pinfunction "GND_6") (pintype "passive"))
      (node (ref "J4") (pin "1") (pinfunction "GND_1") (pintype "passive"))
      (node (ref "Q1") (pin "2") (pinfunction "S_2") (pintype "bidirectional"))
      (node (ref "Q2") (pin "2") (pinfunction "C-_2") (pintype "passive"))
      (node (ref "Q3") (pin "2") (pinfunction "C-_2") (pintype "passive"))
      (node (ref "Q4") (pin "2") (pinfunction "E_2") (pintype "bidirectional"))
      (node (ref "R1") (pin "P$1") (pinfunction "P$1_P$1") (pintype "passive"))
      (node (ref "R14") (pin "P$1") (pinfunction "P$1_P$1") (pintype "passive"))
      (node (ref "R16") (pin "P$1") (pinfunction "P$1_P$1") (pintype "passive"))
      (node (ref "R18") (pin "P$1") (pinfunction "P$1_P$1") (pintype "passive"))
      (node (ref "R20") (pin "P$1") (pinfunction "P$1_P$1") (pintype "passive"))
      (node (ref "R22") (pin "P$1") (pinfunction "P$1_P$1") (pintype "passive"))
      (node (ref "R24") (pin "P$1") (pinfunction "P$1_P$1") (pintype "passive"))
      (node (ref "R33") (pin "P$1") (pinfunction "P$1_P$1") (pintype "passive"))
      (node (ref "R34") (pin "P$1") (pinfunction "P$1_P$1") (pintype "passive"))
      (node (ref "R38") (pin "P$1") (pinfunction "P$1_P$1") (pintype "passive"))
      (node (ref "R39") (pin "P$1") (pinfunction "P$1_P$1") (pintype "passive"))
      (node (ref "R40") (pin "P$1") (pinfunction "P$1_P$1") (pintype "passive"))
      (node (ref "R41") (pin "P$1") (pinfunction "P$1_P$1") (pintype "passive"))
      (node (ref "R45") (pin "P$1") (pinfunction "P$1_P$1") (pintype "passive"))
      (node (ref "R46") (pin "P$1") (pinfunction "P$1_P$1") (pintype "passive"))
      (node (ref "R5") (pin "P$1") (pinfunction "P$1_P$1") (pintype "passive"))
      (node (ref "R54") (pin "P$1") (pinfunction "P$1_P$1") (pintype "passive"))
      (node (ref "R6") (pin "P$1") (pinfunction "P$1_P$1") (pintype "passive"))
      (node (ref "RV1") (pin "3") (pinfunction "CW_3") (pintype "passive"))
      (node (ref "S1") (pin "S1") (pinfunction "GND_S1") (pintype "passive"))
      (node (ref "S1") (pin "S2") (pinfunction "GND_S2") (pintype "passive"))
      (node (ref "S10") (pin "1") (pinfunction "1_1") (pintype "passive"))
      (node (ref "S10") (pin "2") (pinfunction "2_2") (pintype "passive"))
      (node (ref "S11") (pin "1") (pinfunction "1_1") (pintype "passive"))
      (node (ref "S11") (pin "2") (pinfunction "2_2") (pintype "passive"))
      (node (ref "S12") (pin "1") (pinfunction "1_1") (pintype "passive"))
      (node (ref "S12") (pin "2") (pinfunction "2_2") (pintype "passive"))
      (node (ref "S13") (pin "1") (pinfunction "1_1") (pintype "passive"))
      (node (ref "S13") (pin "2") (pinfunction "2_2") (pintype "passive"))
      (node (ref "S2") (pin "1") (pinfunction "1_1") (pintype "passive"))
      (node (ref "S2") (pin "2") (pinfunction "2_2") (pintype "passive"))
      (node (ref "S3") (pin "1") (pinfunction "1_1") (pintype "passive"))
      (node (ref "S3") (pin "2") (pinfunction "2_2") (pintype "passive"))
      (node (ref "S4") (pin "1") (pinfunction "1_1") (pintype "passive"))
      (node (ref "S4") (pin "2") (pinfunction "2_2") (pintype "passive"))
      (node (ref "S5") (pin "1") (pinfunction "1_1") (pintype "passive"))
      (node (ref "S5") (pin "2") (pinfunction "2_2") (pintype "passive"))
      (node (ref "S6") (pin "1") (pinfunction "1_1") (pintype "passive"))
      (node (ref "S6") (pin "2") (pinfunction "2_2") (pintype "passive"))
      (node (ref "S7") (pin "1") (pinfunction "1_1") (pintype "passive"))
      (node (ref "S7") (pin "2") (pinfunction "2_2") (pintype "passive"))
      (node (ref "S8") (pin "1") (pinfunction "1_1") (pintype "passive"))
      (node (ref "S8") (pin "2") (pinfunction "2_2") (pintype "passive"))
      (node (ref "S9") (pin "1") (pinfunction "1_1") (pintype "passive"))
      (node (ref "S9") (pin "2") (pinfunction "2_2") (pintype "passive"))
      (node (ref "U1") (pin "1") (pinfunction "GND_1") (pintype "passive"))
      (node (ref "U1") (pin "9") (pinfunction "GND_9") (pintype "passive"))
      (node (ref "U2") (pin "21") (pinfunction "GND_21") (pintype "passive"))
      (node (ref "U2") (pin "5") (pinfunction "GND_5") (pintype "passive"))
      (node (ref "U3") (pin "2") (pinfunction "GND_2") (pintype "passive"))
      (node (ref "U3") (pin "3") (pinfunction "GND_3") (pintype "passive"))
      (node (ref "U3") (pin "5") (pinfunction "GND_5") (pintype "passive"))
      (node (ref "U4") (pin "18") (pinfunction "GND_18") (pintype "passive"))
      (node (ref "U4") (pin "21") (pinfunction "GND_21") (pintype "passive"))
      (node (ref "U5") (pin "25") (pinfunction "GND_25") (pintype "passive"))
      (node (ref "U5") (pin "9") (pinfunction "GND_9") (pintype "passive"))
      (node (ref "U6") (pin "4") (pinfunction "GND_4") (pintype "passive"))
      (node (ref "U7") (pin "4") (pinfunction "GND_4") (pintype "passive"))
      (node (ref "U8") (pin "1") (pinfunction "GND_1") (pintype "passive"))
      (node (ref "U8") (pin "9") (pinfunction "GND_9") (pintype "passive"))
      (node (ref "XTAL1") (pin "1") (pinfunction "GND_1") (pintype "passive"))
      (node (ref "XTAL1") (pin "3") (pinfunction "GND_3") (pintype "passive"))
      (node (ref "Z1") (pin "2") (pinfunction "CENTER_2") (pintype "passive"))
      (node (ref "Z1") (pin "4") (pinfunction "GND_4") (pintype "passive"))
    )
    (net (code "27") (name "LCD_SCLK") (class "Default")
      (node (ref "A1") (pin "P6") (pinfunction "E/SCLK_P6") (pintype "input"))
      (node (ref "U2") (pin "2") (pinfunction "PD4_2") (pintype "bidirectional"))
    )
    (net (code "28") (name "LCD_SID") (class "Default")
      (node (ref "A1") (pin "P5") (pinfunction "R/~{W}/SID_P5") (pintype "input"))
      (node (ref "U2") (pin "31") (pinfunction "PD1_31") (pintype "bidirectional"))
    )
    (net (code "29") (name "LED0") (class "Default")
      (node (ref "D1") (pin "P$2") (pinfunction "OUT_P$2") (pintype "passive"))
      (node (ref "R26") (pin "P$1") (pinfunction "P$1_P$1") (pintype "passive"))
      (node (ref "U5") (pin "1") (pinfunction "P0_0_1") (pintype "bidirectional"))
    )
    (net (code "30") (name "LED1") (class "Default")
      (node (ref "D2") (pin "P$2") (pinfunction "OUT_P$2") (pintype "passive"))
      (node (ref "R28") (pin "P$1") (pinfunction "P$1_P$1") (pintype "passive"))
      (node (ref "U5") (pin "2") (pinfunction "P0_1_2") (pintype "bidirectional"))
    )
    (net (code "31") (name "LED2") (class "Default")
      (node (ref "D3") (pin "P$2") (pinfunction "OUT_P$2") (pintype "passive"))
      (node (ref "R30") (pin "P$1") (pinfunction "P$1_P$1") (pintype "passive"))
      (node (ref "U5") (pin "3") (pinfunction "P0_2_3") (pintype "bidirectional"))
    )
    (net (code "32") (name "LED3") (class "Default")
      (node (ref "D4") (pin "P$2") (pinfunction "OUT_P$2") (pintype "passive"))
      (node (ref "R32") (pin "P$1") (pinfunction "P$1_P$1") (pintype "passive"))
      (node (ref "U5") (pin "4") (pinfunction "P0_3_4") (pintype "bidirectional"))
    )
    (net (code "33") (name "MISO") (class "Default")
      (node (ref "J1") (pin "1") (pinfunction "MISO_1") (pintype "input"))
      (node (ref "R44") (pin "P$2") (pinfunction "P$2_P$2") (pintype "passive"))
      (node (ref "U2") (pin "16") (pinfunction "PB4_16") (pintype "bidirectional"))
      (node (ref "U4") (pin "13") (pinfunction "SDO_13") (pintype "output"))
    )
    (net (code "34") (name "MOSI") (class "Default")
      (node (ref "J1") (pin "4") (pinfunction "MOSI_4") (pintype "output"))
      (node (ref "U2") (pin "15") (pinfunction "PB3_15") (pintype "bidirectional"))
      (node (ref "U4") (pin "14") (pinfunction "SDI_14") (pintype "input"))
    )
    (net (code "35") (name "Net-(A1-A)") (class "Default")
      (node (ref "A1") (pin "P19") (pinfunction "A_P19") (pintype "power_in"))
      (node (ref "C23") (pin "P$2") (pinfunction "P$2_P$2") (pintype "passive"))
      (node (ref "R47") (pin "P$1") (pinfunction "P$1_P$1") (pintype "passive"))
      (node (ref "R48") (pin "P$1") (pinfunction "P$1_P$1") (pintype "passive"))
    )
    (net (code "36") (name "Net-(A1-P~{S}B)") (class "Default")
      (node (ref "A1") (pin "P15") (pinfunction "P~{S}B_P15") (pintype "input"))
      (node (ref "R38") (pin "P$2") (pinfunction "P$2_P$2") (pintype "passive"))
    )
    (net (code "37") (name "Net-(A1-RS{slash}CS)") (class "Default")
      (node (ref "A1") (pin "P4") (pinfunction "RS/CS_P4") (pintype "input"))
      (node (ref "R36") (pin "P$1") (pinfunction "P$1_P$1") (pintype "passive"))
    )
    (net (code "38") (name "Net-(A1-V0)") (class "Default")
      (node (ref "A1") (pin "P3") (pinfunction "V0_P3") (pintype "power_in"))
      (node (ref "RV1") (pin "2") (pinfunction "WIPER_2") (pintype "passive"))
    )
    (net (code "39") (name "Net-(A1-~{RST})") (class "Default")
      (node (ref "A1") (pin "P17") (pinfunction "~{RST}_P17") (pintype "input"))
      (node (ref "R37") (pin "P$1") (pinfunction "P$1_P$1") (pintype "passive"))
    )
    (net (code "40") (name "Net-(AE1-OUT)") (class "Default")
      (node (ref "AE1") (pin "CENTER") (pinfunction "OUT_CENTER") (pintype "output"))
      (node (ref "C19") (pin "1") (pinfunction "P$1_1") (pintype "passive"))
    )
    (net (code "41") (name "Net-(BT1-+-Pad+1)") (class "Default")
      (node (ref "BT1") (pin "+1") (pinfunction "+_+1") (pintype "power_in"))
      (node (ref "BT1") (pin "+2") (pinfunction "+_+2") (pintype "power_in"))
      (node (ref "BT1") (pin "+3") (pinfunction "+_+3") (pintype "power_in"))
      (node (ref "BT2") (pin "-1") (pinfunction "-_-1") (pintype "passive"))
      (node (ref "BT2") (pin "-2") (pinfunction "-_-2") (pintype "passive"))
      (node (ref "BT2") (pin "-3") (pinfunction "-_-3") (pintype "passive"))
      (node (ref "R51") (pin "P$1") (pinfunction "P$1_P$1") (pintype "passive"))
    )
    (net (code "42") (name "Net-(BT2-+-Pad+1)") (class "Default")
      (node (ref "BT2") (pin "+1") (pinfunction "+_+1") (pintype "power_in"))
      (node (ref "BT2") (pin "+2") (pinfunction "+_+2") (pintype "power_in"))
      (node (ref "BT2") (pin "+3") (pinfunction "+_+3") (pintype "power_in"))
      (node (ref "R51") (pin "P$2") (pinfunction "P$2_P$2") (pintype "passive"))
      (node (ref "RV3") (pin "P$1") (pinfunction "P$1_P$1") (pintype "passive"))
    )
    (net (code "43") (name "Net-(C3-PadP$2)") (class "Default")
      (node (ref "C3") (pin "P$2") (pinfunction "P$2_P$2") (pintype "passive"))
      (node (ref "R3") (pin "P$1") (pinfunction "P$1_P$1") (pintype "passive"))
    )
    (net (code "44") (name "Net-(C19-P$2)") (class "Default")
      (node (ref "C19") (pin "2") (pinfunction "P$2_2") (pintype "passive"))
      (node (ref "Z1") (pin "6") (pinfunction "UNBAL_6") (pintype "passive"))
    )
    (net (code "45") (name "Net-(C37-PadP$2)") (class "Default")
      (node (ref "C37") (pin "P$2") (pinfunction "P$2_P$2") (pintype "passive"))
      (node (ref "R52") (pin "P$1") (pinfunction "P$1_P$1") (pintype "passive"))
    )
    (net (code "46") (name "Net-(D1-IN)") (class "Default")
      (node (ref "D1") (pin "P$1") (pinfunction "IN_P$1") (pintype "passive"))
      (node (ref "R25") (pin "P$2") (pinfunction "P$2_P$2") (pintype "passive"))
    )
    (net (code "47") (name "Net-(D2-IN)") (class "Default")
      (node (ref "D2") (pin "P$1") (pinfunction "IN_P$1") (pintype "passive"))
      (node (ref "R27") (pin "P$2") (pinfunction "P$2_P$2") (pintype "passive"))
    )
    (net (code "48") (name "Net-(D3-IN)") (class "Default")
      (node (ref "D3") (pin "P$1") (pinfunction "IN_P$1") (pintype "passive"))
      (node (ref "R29") (pin "P$2") (pinfunction "P$2_P$2") (pintype "passive"))
    )
    (net (code "49") (name "Net-(D4-IN)") (class "Default")
      (node (ref "D4") (pin "P$1") (pinfunction "IN_P$1") (pintype "passive"))
      (node (ref "R31") (pin "P$2") (pinfunction "P$2_P$2") (pintype "passive"))
    )
    (net (code "50") (name "Net-(J1-VCC)") (class "Default")
      (node (ref "C25") (pin "P$1") (pinfunction "P$1_P$1") (pintype "passive"))
      (node (ref "J1") (pin "2") (pinfunction "VCC_2") (pintype "power_in"))
      (node (ref "R7") (pin "P$1") (pinfunction "P$1_P$1") (pintype "passive"))
    )
    (net (code "51") (name "Net-(J2-8-Pad18)") (class "Default")
      (node (ref "J2") (pin "18") (pinfunction "8_18") (pintype "power_in"))
      (node (ref "J2") (pin "8") (pinfunction "8_8") (pintype "power_in"))
      (node (ref "RV5") (pin "P$2") (pinfunction "P$2_P$2") (pintype "passive"))
    )
    (net (code "52") (name "Net-(J3-VCC)") (class "Default")
      (node (ref "C26") (pin "P$1") (pinfunction "P$1_P$1") (pintype "passive"))
      (node (ref "J3") (pin "2") (pinfunction "VCC_2") (pintype "power_in"))
      (node (ref "R8") (pin "P$1") (pinfunction "P$1_P$1") (pintype "passive"))
    )
    (net (code "53") (name "Net-(LS1-P$1)") (class "Default")
      (node (ref "LS1") (pin "1") (pinfunction "P$1_1") (pintype "passive"))
      (node (ref "Q4") (pin "3") (pinfunction "C_3") (pintype "bidirectional"))
      (node (ref "R13") (pin "P$1") (pinfunction "P$1_P$1") (pintype "passive"))
    )
    (net (code "54") (name "Net-(Q1-D)") (class "Default")
      (node (ref "BT1") (pin "-1") (pinfunction "-_-1") (pintype "passive"))
      (node (ref "BT1") (pin "-2") (pinfunction "-_-2") (pintype "passive"))
      (node (ref "BT1") (pin "-3") (pinfunction "-_-3") (pintype "passive"))
      (node (ref "C1") (pin "P$1") (pinfunction "P$1_P$1") (pintype "passive"))
      (node (ref "Q1") (pin "3") (pinfunction "D_3") (pintype "bidirectional"))
      (node (ref "R1") (pin "P$2") (pinfunction "P$2_P$2") (pintype "passive"))
    )
    (net (code "55") (name "Net-(Q2-C+)") (class "Default")
      (node (ref "Q2") (pin "1") (pinfunction "C+_1") (pintype "input"))
      (node (ref "R9") (pin "P$1") (pinfunction "P$1_P$1") (pintype "passive"))
    )
    (net (code "56") (name "Net-(Q3-C+)") (class "Default")
      (node (ref "Q3") (pin "1") (pinfunction "C+_1") (pintype "input"))
      (node (ref "R12") (pin "P$1") (pinfunction "P$1_P$1") (pintype "passive"))
    )
    (net (code "57") (name "Net-(Q3-DC+)") (class "Default")
      (node (ref "Q3") (pin "4") (pinfunction "DC+_4") (pintype "power_in"))
      (node (ref "RV2") (pin "P$1") (pinfunction "P$1_P$1") (pintype "passive"))
    )
    (net (code "58") (name "Net-(R2-PadP$1)") (class "Default")
      (node (ref "R2") (pin "P$1") (pinfunction "P$1_P$1") (pintype "passive"))
      (node (ref "S1") (pin "2") (pinfunction "2_2") (pintype "passive"))
    )
    (net (code "59") (name "Net-(U1-BST)") (class "Default")
      (node (ref "C5") (pin "P$2") (pinfunction "P$2_P$2") (pintype "passive"))
      (node (ref "U1") (pin "8") (pinfunction "BST_8") (pintype "passive"))
    )
    (net (code "60") (name "Net-(U1-COMP)") (class "Default")
      (node (ref "R3") (pin "P$2") (pinfunction "P$2_P$2") (pintype "passive"))
      (node (ref "U1") (pin "4") (pinfunction "COMP_4") (pintype "passive"))
    )
    (net (code "61") (name "Net-(U1-FB)") (class "Default")
      (node (ref "R4") (pin "P$1") (pinfunction "P$1_P$1") (pintype "passive"))
      (node (ref "R5") (pin "P$2") (pinfunction "P$2_P$2") (pintype "passive"))
      (node (ref "U1") (pin "6") (pinfunction "FB_6") (pintype "input"))
    )
    (net (code "62") (name "Net-(U1-LX)") (class "Default")
      (node (ref "C5") (pin "P$1") (pinfunction "P$1_P$1") (pintype "passive"))
      (node (ref "L1") (pin "P$1") (pinfunction "P$1_P$1") (pintype "passive"))
      (node (ref "U1") (pin "2") (pinfunction "LX_2") (pintype "output"))
    )
    (net (code "63") (name "Net-(U1-VCC)") (class "Default")
      (node (ref "C4") (pin "P$2") (pinfunction "P$2_P$2") (pintype "passive"))
      (node (ref "U1") (pin "5") (pinfunction "VCC_5") (pintype "passive"))
    )
    (net (code "64") (name "Net-(U1-VIN)") (class "Default")
      (node (ref "C2") (pin "P$2") (pinfunction "P$2_P$2") (pintype "passive"))
      (node (ref "R49") (pin "P$1") (pinfunction "P$1_P$1") (pintype "passive"))
      (node (ref "R50") (pin "P$1") (pinfunction "P$1_P$1") (pintype "passive"))
      (node (ref "U1") (pin "3") (pinfunction "VIN_3") (pintype "power_in"))
    )
    (net (code "65") (name "Net-(U3-~{SHDN})") (class "Default")
      (node (ref "R14") (pin "P$2") (pinfunction "P$2_P$2") (pintype "passive"))
      (node (ref "U3") (pin "4") (pinfunction "~{SHDN}_4") (pintype "input"))
    )
    (net (code "66") (name "Net-(U4-RXN)") (class "Default")
      (node (ref "U4") (pin "3") (pinfunction "RXN_3") (pintype "passive"))
      (node (ref "Z1") (pin "3") (pinfunction "BAL2_3") (pintype "passive"))
    )
    (net (code "67") (name "Net-(U4-RXP)") (class "Default")
      (node (ref "U4") (pin "2") (pinfunction "RXP_2") (pintype "passive"))
      (node (ref "Z1") (pin "1") (pinfunction "BAL1_1") (pintype "passive"))
    )
    (net (code "68") (name "Net-(U4-SDN)") (class "Default")
      (node (ref "R33") (pin "P$2") (pinfunction "P$2_P$2") (pintype "passive"))
      (node (ref "U4") (pin "1") (pinfunction "SDN_1") (pintype "input"))
    )
    (net (code "69") (name "Net-(U4-XIN)") (class "Default")
      (node (ref "C17") (pin "P$2") (pinfunction "P$2_P$2") (pintype "passive"))
      (node (ref "C41") (pin "P$1") (pinfunction "P$1_P$1") (pintype "passive"))
      (node (ref "U4") (pin "17") (pinfunction "XIN_17") (pintype "input"))
      (node (ref "XTAL1") (pin "2") (pinfunction "P$1_2") (pintype "passive"))
    )
    (net (code "70") (name "Net-(U4-XOUT)") (class "Default")
      (node (ref "C18") (pin "P$2") (pinfunction "P$2_P$2") (pintype "passive"))
      (node (ref "C41") (pin "P$2") (pinfunction "P$2_P$2") (pintype "passive"))
      (node (ref "U4") (pin "16") (pinfunction "XOUT_16") (pintype "output"))
      (node (ref "XTAL1") (pin "4") (pinfunction "P$2_4") (pintype "passive"))
    )
    (net (code "71") (name "Net-(U5-ADDR)") (class "Default")
      (node (ref "R34") (pin "P$2") (pinfunction "P$2_P$2") (pintype "passive"))
      (node (ref "U5") (pin "18") (pinfunction "ADDR_18") (pintype "input"))
    )
    (net (code "72") (name "Net-(U5-~{RESET})") (class "Default")
      (node (ref "R35") (pin "P$1") (pinfunction "P$1_P$1") (pintype "passive"))
      (node (ref "U5") (pin "24") (pinfunction "~{RESET}_24") (pintype "input"))
    )
    (net (code "73") (name "Net-(U6-E0)") (class "Default")
      (node (ref "R42") (pin "P$1") (pinfunction "P$1_P$1") (pintype "passive"))
      (node (ref "U6") (pin "1") (pinfunction "E0_1") (pintype "input"))
    )
    (net (code "74") (name "Net-(U6-E1)") (class "Default")
      (node (ref "R41") (pin "P$2") (pinfunction "P$2_P$2") (pintype "passive"))
      (node (ref "U6") (pin "2") (pinfunction "E1_2") (pintype "input"))
    )
    (net (code "75") (name "Net-(U6-E2)") (class "Default")
      (node (ref "R40") (pin "P$2") (pinfunction "P$2_P$2") (pintype "passive"))
      (node (ref "U6") (pin "3") (pinfunction "E2_3") (pintype "input"))
    )
    (net (code "76") (name "Net-(U6-~{WC})") (class "Default")
      (node (ref "R39") (pin "P$2") (pinfunction "P$2_P$2") (pintype "passive"))
      (node (ref "R43") (pin "P$1") (pinfunction "P$1_P$1") (pintype "passive"))
      (node (ref "U6") (pin "7") (pinfunction "~{WC}_7") (pintype "input"))
    )
    (net (code "77") (name "Net-(U7-A1)") (class "Default")
      (node (ref "R46") (pin "P$2") (pinfunction "P$2_P$2") (pintype "passive"))
      (node (ref "U7") (pin "2") (pinfunction "A1_2") (pintype "input"))
    )
    (net (code "78") (name "Net-(U7-A2)") (class "Default")
      (node (ref "R45") (pin "P$2") (pinfunction "P$2_P$2") (pintype "passive"))
      (node (ref "U7") (pin "3") (pinfunction "A2_3") (pintype "input"))
    )
    (net (code "79") (name "Net-(U7-HS)") (class "Default")
      (node (ref "R6") (pin "P$2") (pinfunction "P$2_P$2") (pintype "passive"))
      (node (ref "U7") (pin "7") (pinfunction "HS_7") (pintype "input"))
    )
    (net (code "80") (name "Net-(U7-VCAP)") (class "Default")
      (node (ref "C8") (pin "P$2") (pinfunction "P$2_P$2") (pintype "passive"))
      (node (ref "U7") (pin "1") (pinfunction "VCAP_1") (pintype "passive"))
    )
    (net (code "81") (name "Net-(U8-BST)") (class "Default")
      (node (ref "C39") (pin "P$2") (pinfunction "P$2_P$2") (pintype "passive"))
      (node (ref "U8") (pin "8") (pinfunction "BST_8") (pintype "passive"))
    )
    (net (code "82") (name "Net-(U8-COMP)") (class "Default")
      (node (ref "R52") (pin "P$2") (pinfunction "P$2_P$2") (pintype "passive"))
      (node (ref "U8") (pin "4") (pinfunction "COMP_4") (pintype "passive"))
    )
    (net (code "83") (name "Net-(U8-FB)") (class "Default")
      (node (ref "R53") (pin "P$1") (pinfunction "P$1_P$1") (pintype "passive"))
      (node (ref "R54") (pin "P$2") (pinfunction "P$2_P$2") (pintype "passive"))
      (node (ref "U8") (pin "6") (pinfunction "FB_6") (pintype "input"))
    )
    (net (code "84") (name "Net-(U8-LX)") (class "Default")
      (node (ref "C39") (pin "P$1") (pinfunction "P$1_P$1") (pintype "passive"))
      (node (ref "L2") (pin "P$1") (pinfunction "P$1_P$1") (pintype "passive"))
      (node (ref "U8") (pin "2") (pinfunction "LX_2") (pintype "output"))
    )
    (net (code "85") (name "Net-(U8-VCC)") (class "Default")
      (node (ref "C38") (pin "P$2") (pinfunction "P$2_P$2") (pintype "passive"))
      (node (ref "U8") (pin "5") (pinfunction "VCC_5") (pintype "passive"))
    )
    (net (code "86") (name "PWR_EN") (class "Default")
      (node (ref "S1") (pin "3") (pinfunction "3_3") (pintype "passive"))
      (node (ref "U1") (pin "7") (pinfunction "EN_7") (pintype "input"))
      (node (ref "U8") (pin "7") (pinfunction "EN_7") (pintype "input"))
    )
    (net (code "87") (name "SCL") (class "Default")
      (node (ref "J4") (pin "2") (pinfunction "SCL_2") (pintype "bidirectional"))
      (node (ref "R11") (pin "P$1") (pinfunction "P$1_P$1") (pintype "passive"))
      (node (ref "U2") (pin "6") (pinfunction "PE1_6") (pintype "bidirectional"))
      (node (ref "U5") (pin "19") (pinfunction "SCL_19") (pintype "input"))
      (node (ref "U6") (pin "6") (pinfunction "SCL_6") (pintype "input"))
      (node (ref "U7") (pin "6") (pinfunction "SCL_6") (pintype "input"))
    )
    (net (code "88") (name "SCLK") (class "Default")
      (node (ref "J1") (pin "3") (pinfunction "SCK_3") (pintype "output"))
      (node (ref "U2") (pin "17") (pinfunction "PB5_17") (pintype "bidirectional"))
      (node (ref "U4") (pin "12") (pinfunction "SCLK_12") (pintype "input"))
    )
    (net (code "89") (name "SDA") (class "Default")
      (node (ref "J4") (pin "3") (pinfunction "SDA_3") (pintype "bidirectional"))
      (node (ref "R10") (pin "P$1") (pinfunction "P$1_P$1") (pintype "passive"))
      (node (ref "U2") (pin "3") (pinfunction "PE0_3") (pintype "bidirectional"))
      (node (ref "U5") (pin "20") (pinfunction "SDA_20") (pintype "bidirectional"))
      (node (ref "U6") (pin "5") (pinfunction "SDA_5") (pintype "bidirectional"))
      (node (ref "U7") (pin "5") (pinfunction "SDA_5") (pintype "bidirectional"))
    )
    (net (code "90") (name "SLAVE_3V3") (class "Default")
      (node (ref "C26") (pin "P$2") (pinfunction "P$2_P$2") (pintype "passive"))
      (node (ref "J2") (pin "14") (pinfunction "4_14") (pintype "power_in"))
      (node (ref "J2") (pin "4") (pinfunction "4_4") (pintype "power_in"))
      (node (ref "Q3") (pin "3") (pinfunction "DC-_3") (pintype "power_in"))
      (node (ref "R15") (pin "P$2") (pinfunction "P$2_P$2") (pintype "passive"))
      (node (ref "R8") (pin "P$2") (pinfunction "P$2_P$2") (pintype "passive"))
    )
    (net (code "91") (name "SLAVE_3V3_AIN") (class "Default")
      (node (ref "C34") (pin "P$2") (pinfunction "P$2_P$2") (pintype "passive"))
      (node (ref "R15") (pin "P$1") (pinfunction "P$1_P$1") (pintype "passive"))
      (node (ref "R16") (pin "P$2") (pinfunction "P$2_P$2") (pintype "passive"))
      (node (ref "U2") (pin "19") (pinfunction "PE2_19") (pintype "bidirectional"))
    )
    (net (code "92") (name "SLAVE_5V") (class "Default")
      (node (ref "J2") (pin "13") (pinfunction "3_13") (pintype "power_in"))
      (node (ref "J2") (pin "3") (pinfunction "3_3") (pintype "power_in"))
      (node (ref "R19") (pin "P$2") (pinfunction "P$2_P$2") (pintype "passive"))
    )
    (net (code "93") (name "SLAVE_5V_AIN") (class "Default")
      (node (ref "C35") (pin "P$2") (pinfunction "P$2_P$2") (pintype "passive"))
      (node (ref "R19") (pin "P$1") (pinfunction "P$1_P$1") (pintype "passive"))
      (node (ref "R20") (pin "P$2") (pinfunction "P$2_P$2") (pintype "passive"))
      (node (ref "U2") (pin "22") (pinfunction "PE3_22") (pintype "bidirectional"))
    )
    (net (code "94") (name "SLAVE_9V") (class "Default")
      (node (ref "J2") (pin "12") (pinfunction "2_12") (pintype "power_in"))
      (node (ref "J2") (pin "2") (pinfunction "2_2") (pintype "power_in"))
      (node (ref "Q2") (pin "3") (pinfunction "DC-_3") (pintype "power_in"))
      (node (ref "R17") (pin "P$2") (pinfunction "P$2_P$2") (pintype "passive"))
    )
    (net (code "95") (name "SLAVE_9V_AIN") (class "Default")
      (node (ref "C33") (pin "P$2") (pinfunction "P$2_P$2") (pintype "passive"))
      (node (ref "R17") (pin "P$1") (pinfunction "P$1_P$1") (pintype "passive"))
      (node (ref "R18") (pin "P$2") (pinfunction "P$2_P$2") (pintype "passive"))
      (node (ref "U2") (pin "23") (pinfunction "PC0_23") (pintype "bidirectional"))
    )
    (net (code "96") (name "SLAVE_BUZZER") (class "Default")
      (node (ref "RV5") (pin "P$1") (pinfunction "P$1_P$1") (pintype "passive"))
      (node (ref "U2") (pin "9") (pinfunction "PD5_9") (pintype "bidirectional"))
    )
    (net (code "97") (name "SLAVE_MISO") (class "Default")
      (node (ref "R44") (pin "P$1") (pinfunction "P$1_P$1") (pintype "passive"))
      (node (ref "RV7") (pin "P$1") (pinfunction "P$1_P$1") (pintype "passive"))
    )
    (net (code "98") (name "SLAVE_RAW_MISO") (class "Default")
      (node (ref "J2") (pin "16") (pinfunction "6_16") (pintype "power_in"))
      (node (ref "J2") (pin "6") (pinfunction "6_6") (pintype "power_in"))
      (node (ref "J3") (pin "1") (pinfunction "MISO_1") (pintype "input"))
      (node (ref "RV7") (pin "P$2") (pinfunction "P$2_P$2") (pintype "passive"))
    )
    (net (code "99") (name "SLAVE_RAW_SCL") (class "Default")
      (node (ref "J2") (pin "15") (pinfunction "5_15") (pintype "power_in"))
      (node (ref "J2") (pin "5") (pinfunction "5_5") (pintype "power_in"))
      (node (ref "J3") (pin "3") (pinfunction "SCK_3") (pintype "output"))
      (node (ref "RV8") (pin "P$2") (pinfunction "P$2_P$2") (pintype "passive"))
    )
    (net (code "100") (name "SLAVE_RAW_SDA") (class "Default")
      (node (ref "J2") (pin "17") (pinfunction "7_17") (pintype "power_in"))
      (node (ref "J2") (pin "7") (pinfunction "7_7") (pintype "power_in"))
      (node (ref "J3") (pin "4") (pinfunction "MOSI_4") (pintype "output"))
      (node (ref "RV6") (pin "P$2") (pinfunction "P$2_P$2") (pintype "passive"))
    )
    (net (code "101") (name "SLAVE_RLY_3V3") (class "Default")
      (node (ref "R12") (pin "P$2") (pinfunction "P$2_P$2") (pintype "passive"))
      (node (ref "U2") (pin "13") (pinfunction "PB1_13") (pintype "bidirectional"))
    )
    (net (code "102") (name "SLAVE_RLY_9V") (class "Default")
      (node (ref "R9") (pin "P$2") (pinfunction "P$2_P$2") (pintype "passive"))
      (node (ref "U2") (pin "30") (pinfunction "PD0_30") (pintype "bidirectional"))
    )
    (net (code "103") (name "SLAVE_SCL") (class "Default")
      (node (ref "RV8") (pin "P$1") (pinfunction "P$1_P$1") (pintype "passive"))
      (node (ref "U2") (pin "28") (pinfunction "PC5_28") (pintype "bidirectional"))
    )
    (net (code "104") (name "SLAVE_SDA") (class "Default")
      (node (ref "RV6") (pin "P$1") (pinfunction "P$1_P$1") (pintype "passive"))
      (node (ref "U2") (pin "27") (pinfunction "PC4_27") (pintype "bidirectional"))
    )
    (net (code "105") (name "SLAVE_VBAT") (class "Default")
      (node (ref "J2") (pin "1") (pinfunction "1_1") (pintype "power_in"))
      (node (ref "J2") (pin "11") (pinfunction "1_11") (pintype "power_in"))
      (node (ref "Q2") (pin "4") (pinfunction "DC+_4") (pintype "power_in"))
      (node (ref "R21") (pin "P$2") (pinfunction "P$2_P$2") (pintype "passive"))
    )
    (net (code "106") (name "SLAVE_VBAT_AIN") (class "Default")
      (node (ref "C32") (pin "P$2") (pinfunction "P$2_P$2") (pintype "passive"))
      (node (ref "R21") (pin "P$1") (pinfunction "P$1_P$1") (pintype "passive"))
      (node (ref "R22") (pin "P$2") (pinfunction "P$2_P$2") (pintype "passive"))
      (node (ref "U2") (pin "24") (pinfunction "PC1_24") (pintype "bidirectional"))
    )
    (net (code "107") (name "VEE") (class "Default")
      (node (ref "A1") (pin "P18") (pinfunction "VEE_P18") (pintype "power_in"))
    )
    (net (code "108") (name "unconnected-(A1-D0-PadP7)") (class "Default")
      (node (ref "A1") (pin "P7") (pinfunction "D0_P7") (pintype "bidirectional"))
    )
    (net (code "109") (name "unconnected-(A1-D1-PadP8)") (class "Default")
      (node (ref "A1") (pin "P8") (pinfunction "D1_P8") (pintype "bidirectional"))
    )
    (net (code "110") (name "unconnected-(A1-D2-PadP9)") (class "Default")
      (node (ref "A1") (pin "P9") (pinfunction "D2_P9") (pintype "bidirectional"))
    )
    (net (code "111") (name "unconnected-(A1-D3-PadP10)") (class "Default")
      (node (ref "A1") (pin "P10") (pinfunction "D3_P10") (pintype "bidirectional"))
    )
    (net (code "112") (name "unconnected-(A1-D4-PadP11)") (class "Default")
      (node (ref "A1") (pin "P11") (pinfunction "D4_P11") (pintype "bidirectional"))
    )
    (net (code "113") (name "unconnected-(A1-D5-PadP12)") (class "Default")
      (node (ref "A1") (pin "P12") (pinfunction "D5_P12") (pintype "bidirectional"))
    )
    (net (code "114") (name "unconnected-(A1-D6-PadP13)") (class "Default")
      (node (ref "A1") (pin "P13") (pinfunction "D6_P13") (pintype "bidirectional"))
    )
    (net (code "115") (name "unconnected-(A1-D7-PadP14)") (class "Default")
      (node (ref "A1") (pin "P14") (pinfunction "D7_P14") (pintype "bidirectional"))
    )
    (net (code "116") (name "unconnected-(S1-Pad1)") (class "Default")
      (node (ref "S1") (pin "1") (pinfunction "1_1") (pintype "passive"))
    )
    (net (code "117") (name "~{RESET}") (class "Default")
      (node (ref "J1") (pin "5") (pinfunction "~{RST}_5") (pintype "output"))
      (node (ref "R55") (pin "P$1") (pinfunction "P$1_P$1") (pintype "passive"))
      (node (ref "U2") (pin "29") (pinfunction "PC6_29") (pintype "bidirectional"))
    )
    (net (code "118") (name "~{SLAVE_RAW_RESET}") (class "Default")
      (node (ref "J2") (pin "19") (pinfunction "9_19") (pintype "power_in"))
      (node (ref "J2") (pin "9") (pinfunction "9_9") (pintype "power_in"))
      (node (ref "J3") (pin "5") (pinfunction "~{RST}_5") (pintype "output"))
      (node (ref "RV4") (pin "P$2") (pinfunction "P$2_P$2") (pintype "passive"))
    )
    (net (code "119") (name "~{SLAVE_RESET}") (class "Default")
      (node (ref "RV4") (pin "P$1") (pinfunction "P$1_P$1") (pintype "passive"))
      (node (ref "U2") (pin "12") (pinfunction "PB0_12") (pintype "bidirectional"))
    )
  )
)
